# zik-pcb-sbc-ez80stm100p.net
KiCad netlist of a schematic drawn in EAGLE
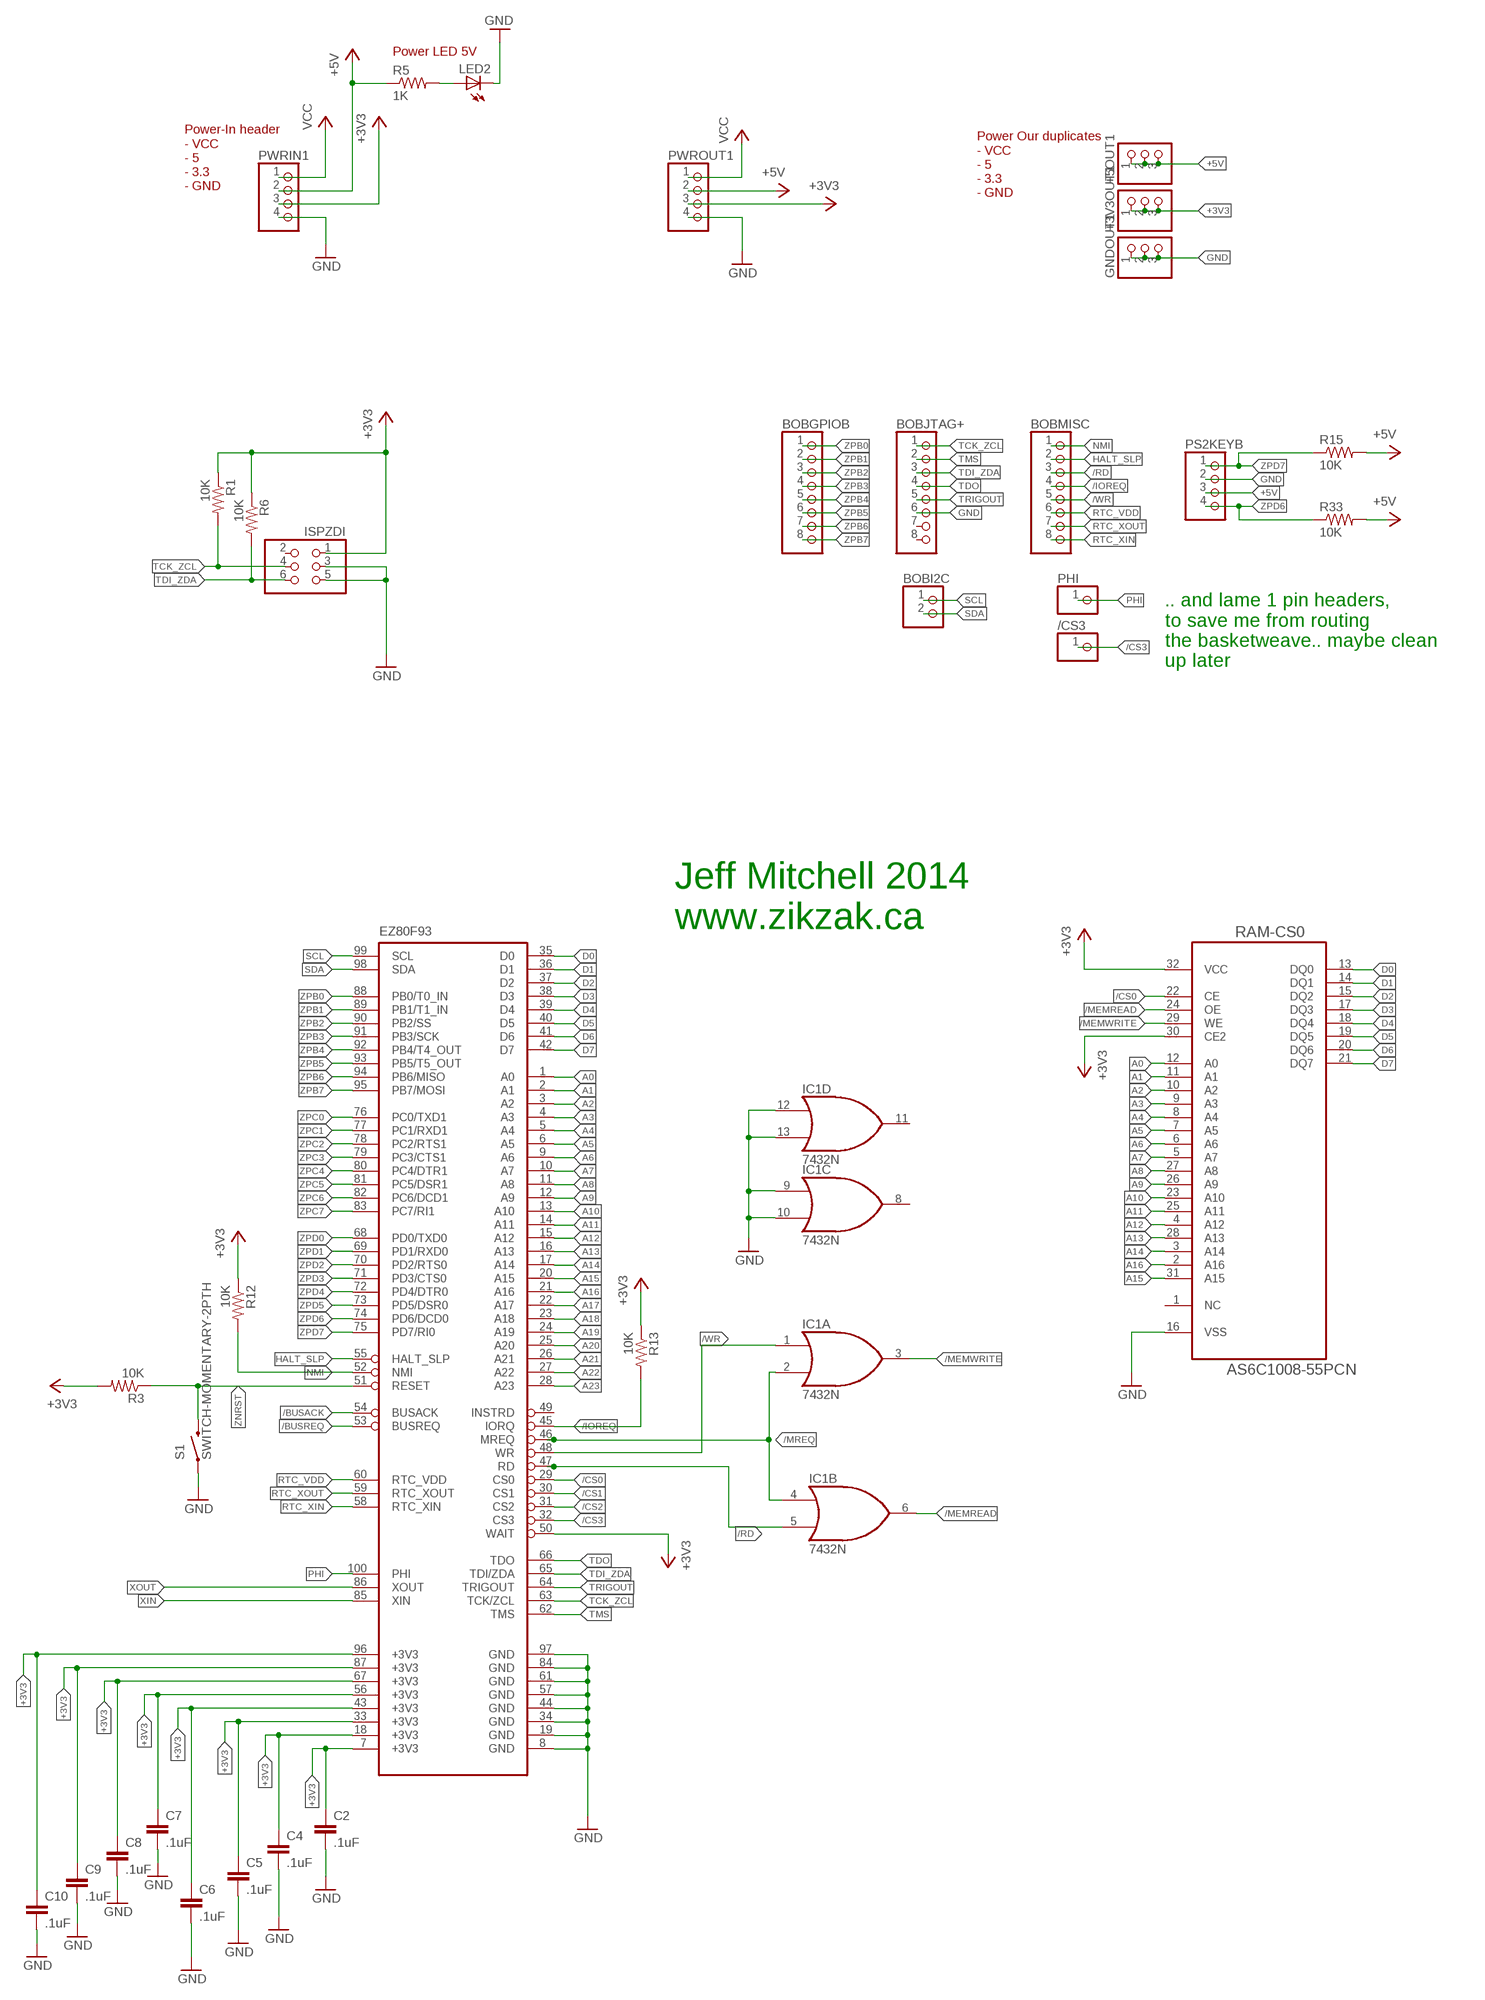
[diagram p0: schematic, sheet 1, part 1 of 3]
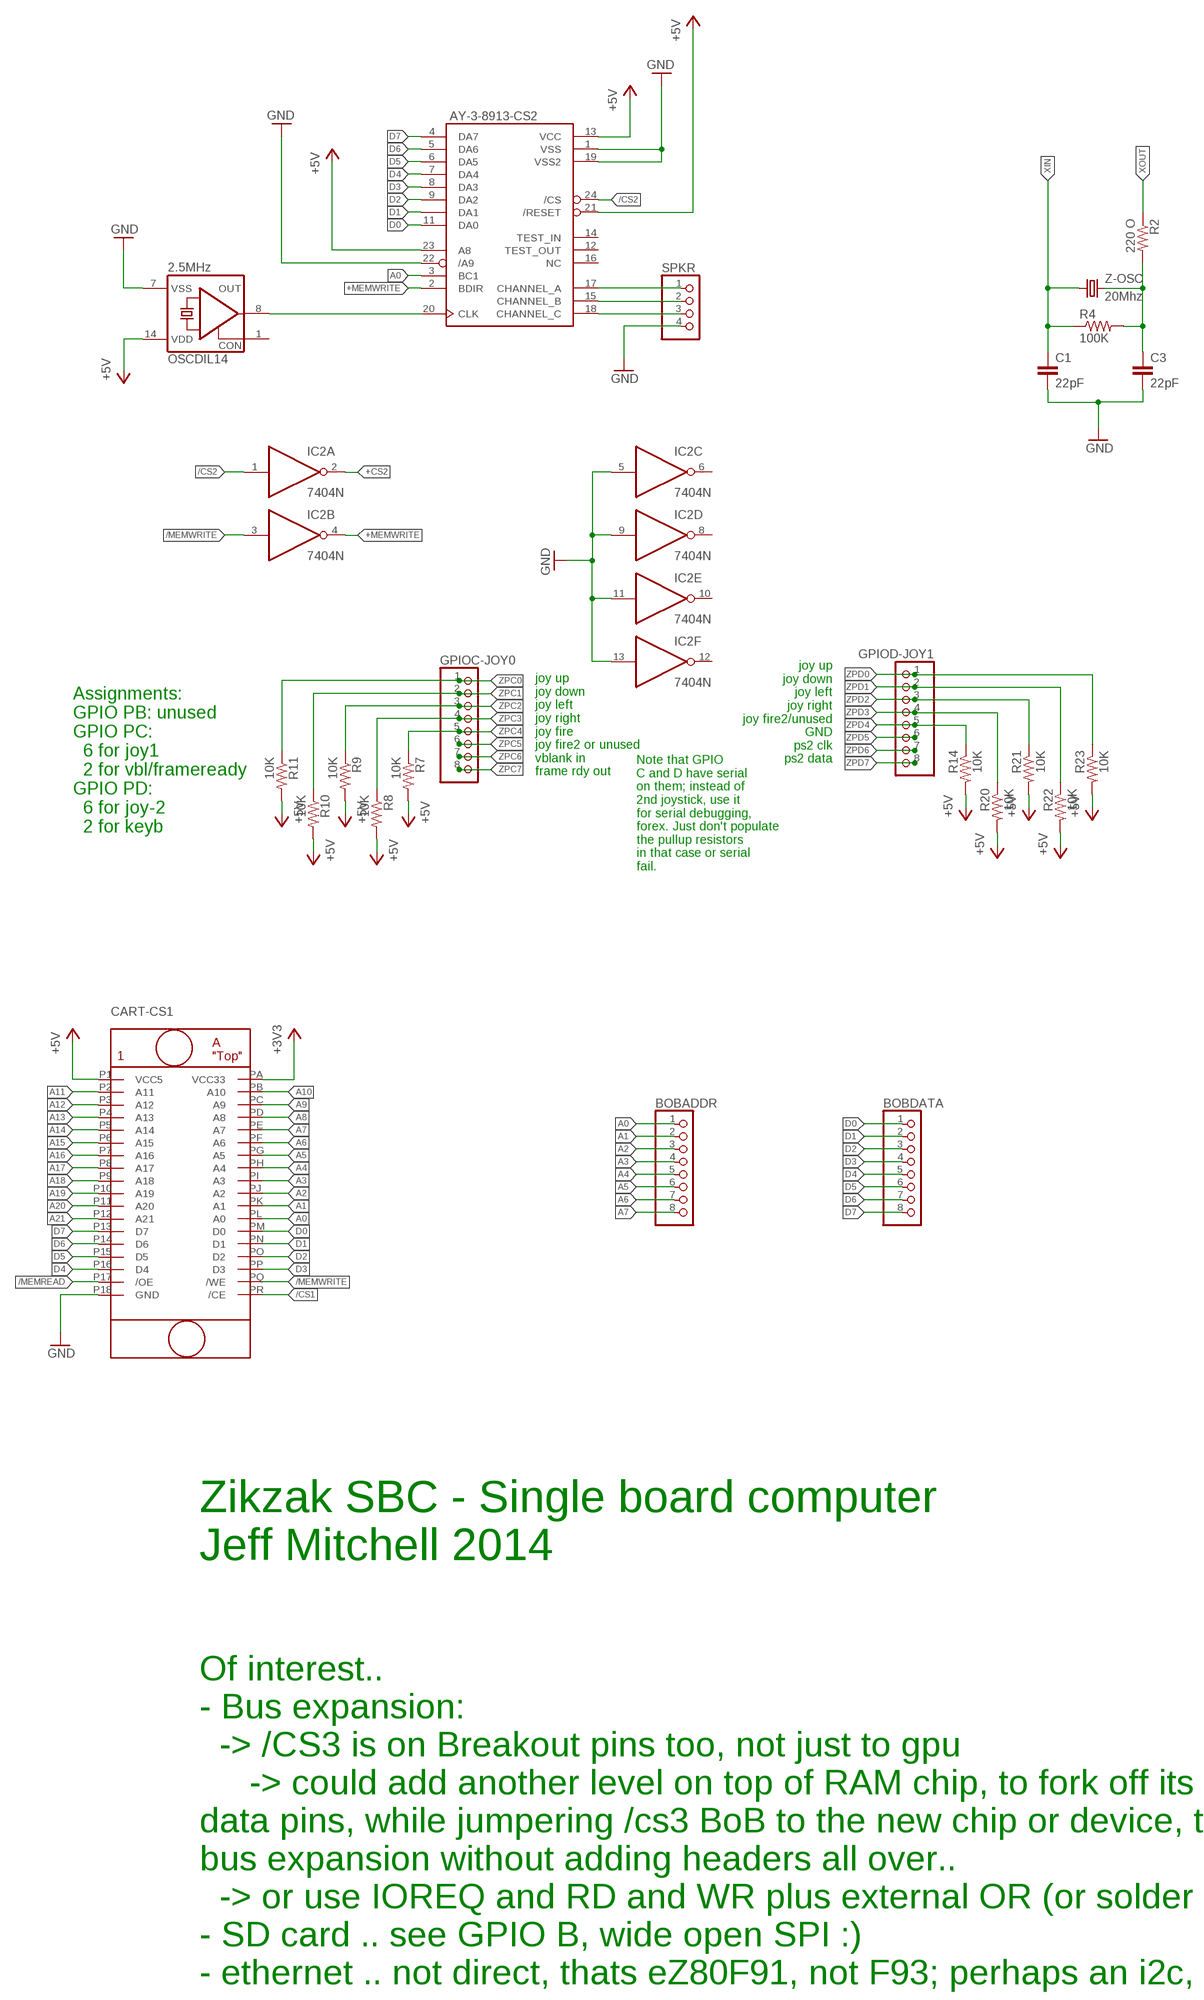
[diagram p1: schematic, sheet 1, part 2 of 3]
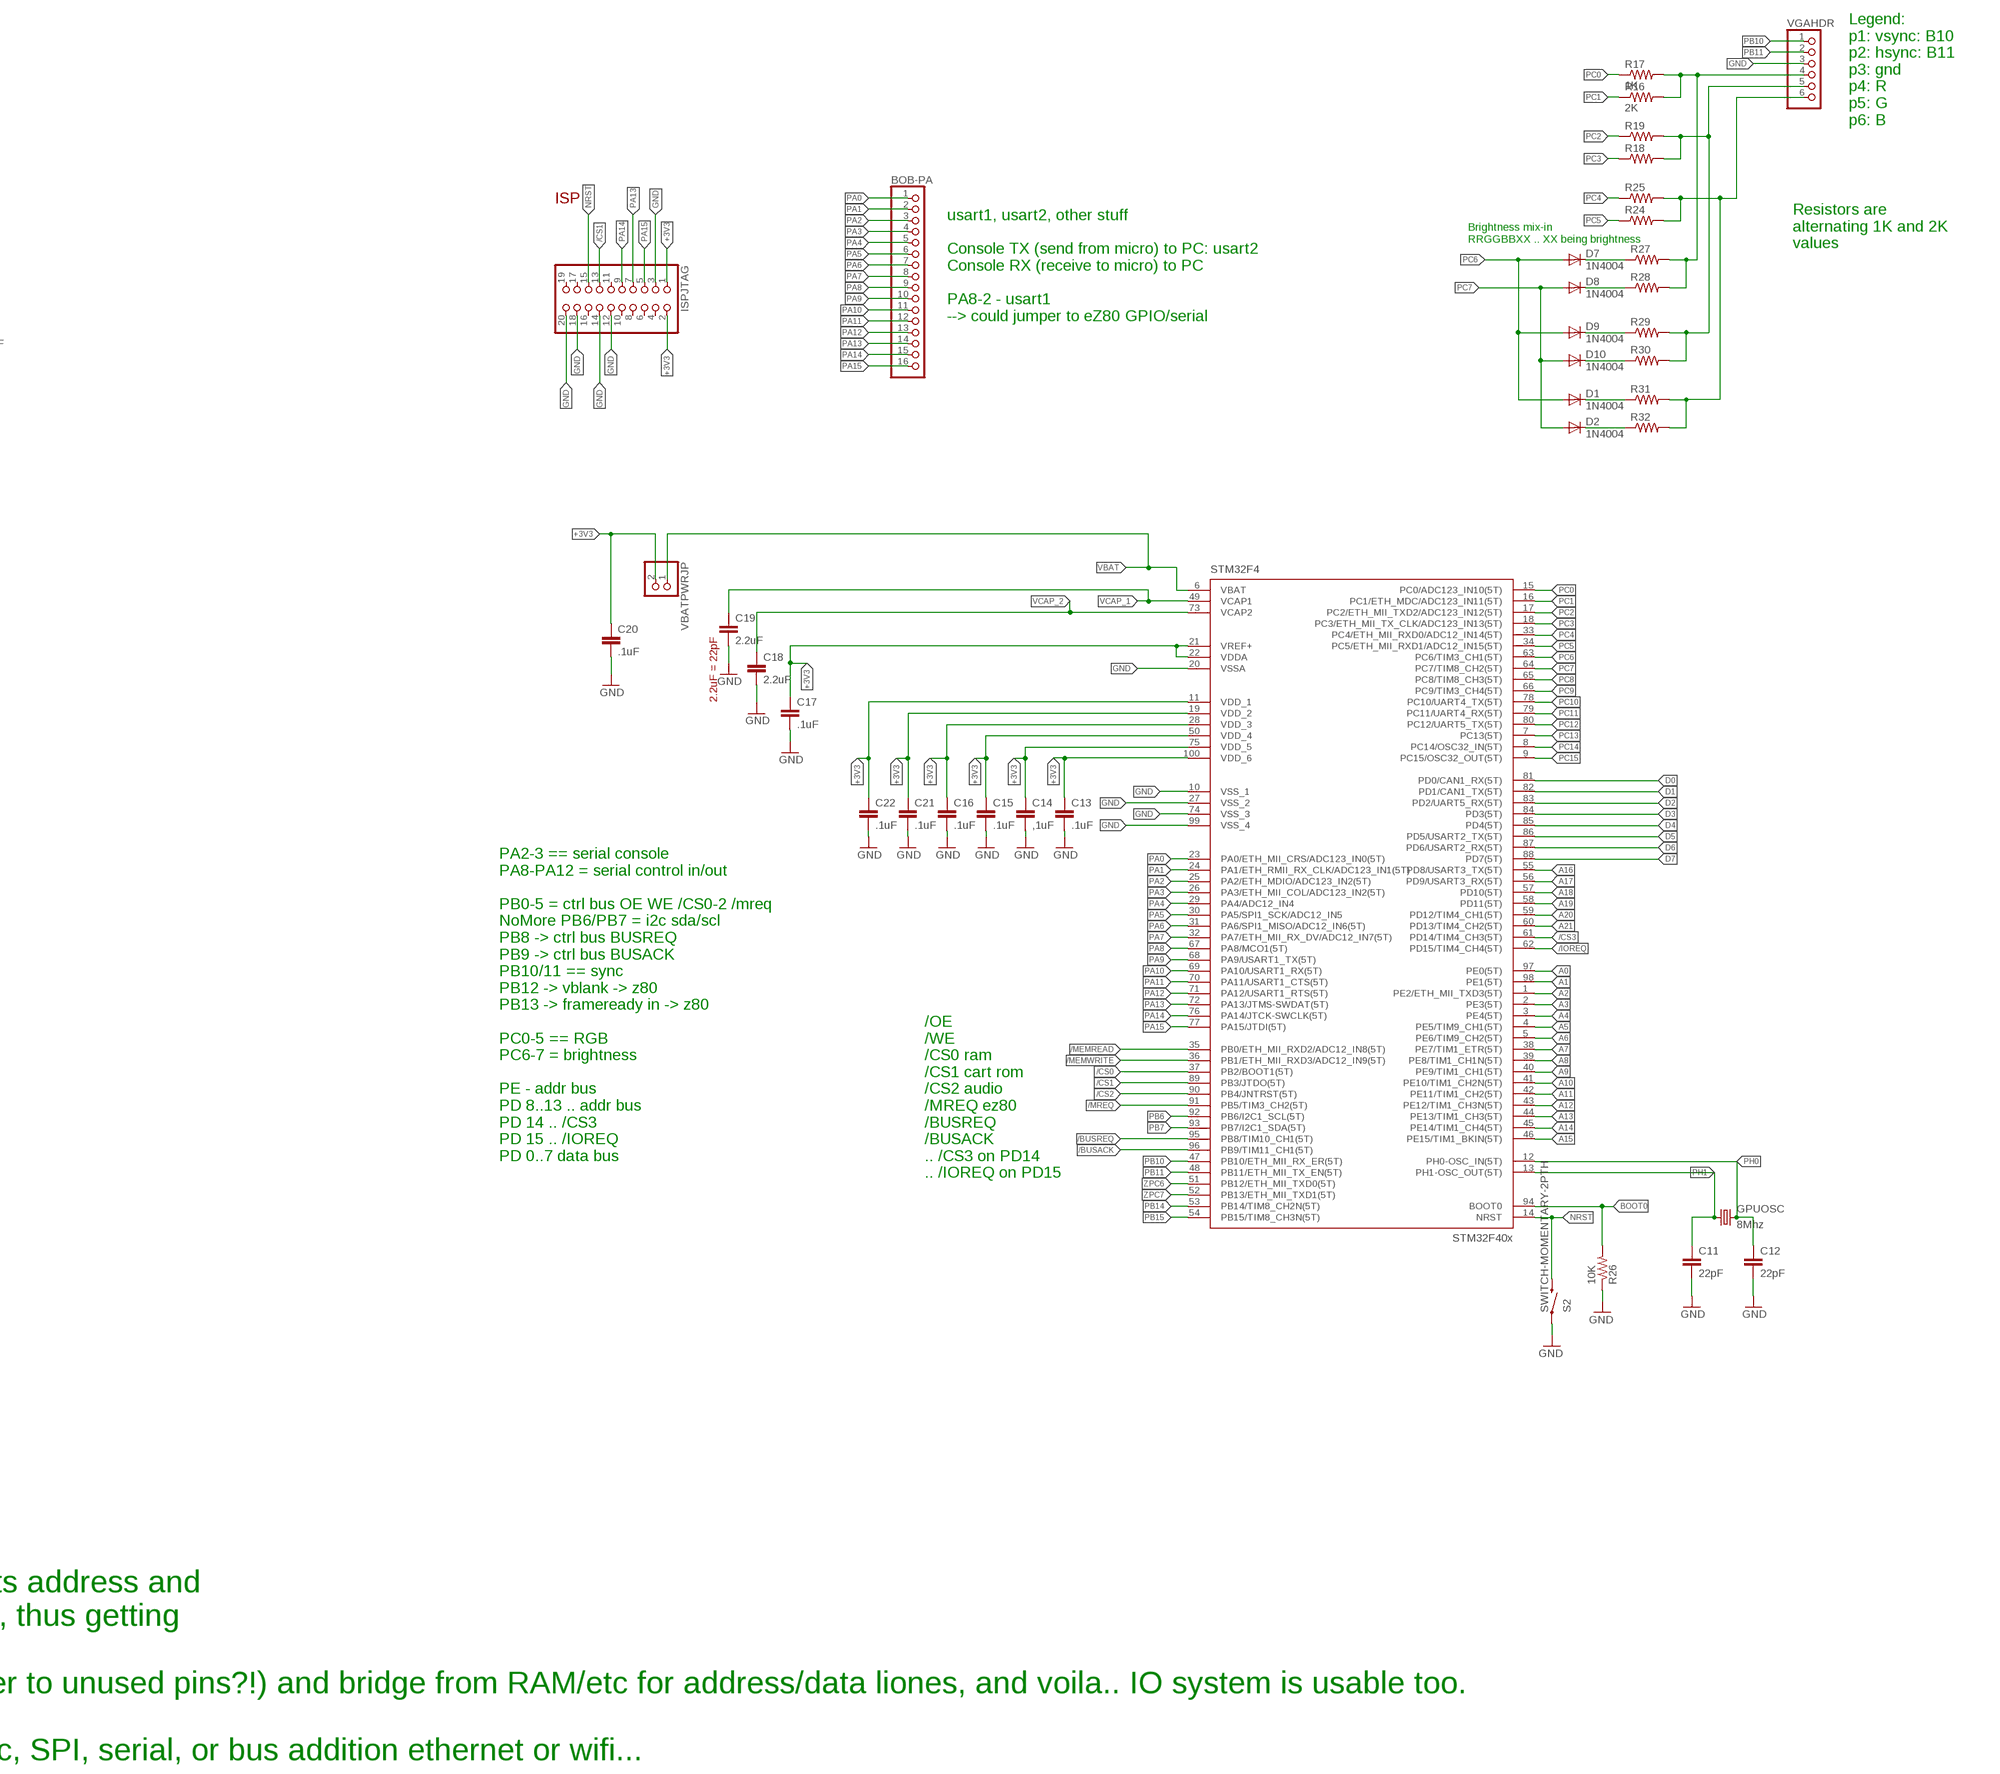
[diagram p2: schematic, sheet 1, part 3 of 3]

(export (version "E")
  (design (tool "Eeschema 10.0.6"))
  (components
    (comp (ref "+3V3OUT1")
      (value "PINHD-1X3")
      (footprint "eagle-import:1X03")
      (libsource (lib "eagle-import") (part "PINHD-1X3"))
    )
    (comp (ref "+5OUT1")
      (value "PINHD-1X3")
      (footprint "eagle-import:1X03")
      (libsource (lib "eagle-import") (part "PINHD-1X3"))
    )
    (comp (ref "/CS3")
      (value "PINHD-1X1")
      (footprint "eagle-import:1X01")
      (libsource (lib "eagle-import") (part "PINHD-1X1"))
    )
    (comp (ref "AY-3-8913-CS2")
      (value "AY-3-8912_24PIN-6")
      (footprint "eagle-import:DIL24-6")
      (libsource (lib "eagle-import") (part "AY-3-8912_24PIN-6"))
    )
    (comp (ref "BOB-PA")
      (value "PINHD-1X16")
      (footprint "eagle-import:1X16")
      (libsource (lib "eagle-import") (part "PINHD-1X16"))
    )
    (comp (ref "BOBADDR")
      (value "PINHD-1X8")
      (footprint "eagle-import:1X08")
      (libsource (lib "eagle-import") (part "PINHD-1X8"))
    )
    (comp (ref "BOBDATA")
      (value "PINHD-1X8")
      (footprint "eagle-import:1X08")
      (libsource (lib "eagle-import") (part "PINHD-1X8"))
    )
    (comp (ref "BOBGPIOB")
      (value "PINHD-1X8")
      (footprint "eagle-import:1X08")
      (libsource (lib "eagle-import") (part "PINHD-1X8"))
    )
    (comp (ref "BOBI2C")
      (value "PINHD-1X2")
      (footprint "eagle-import:1X02")
      (libsource (lib "eagle-import") (part "PINHD-1X2"))
    )
    (comp (ref "BOBJTAG+")
      (value "PINHD-1X8")
      (footprint "eagle-import:1X08")
      (libsource (lib "eagle-import") (part "PINHD-1X8"))
    )
    (comp (ref "BOBMISC")
      (value "PINHD-1X8")
      (footprint "eagle-import:1X08")
      (libsource (lib "eagle-import") (part "PINHD-1X8"))
    )
    (comp (ref "C1")
      (value "22pF")
      (footprint "eagle-import:C025-025X050")
      (libsource (lib "eagle-import") (part "C-EU025-025X050"))
    )
    (comp (ref "C2")
      (value ".1uF")
      (footprint "eagle-import:C025-025X050")
      (libsource (lib "eagle-import") (part "C-EU025-025X050"))
    )
    (comp (ref "C3")
      (value "22pF")
      (footprint "eagle-import:C025-025X050")
      (libsource (lib "eagle-import") (part "C-EU025-025X050"))
    )
    (comp (ref "C4")
      (value ".1uF")
      (footprint "eagle-import:C025-025X050")
      (libsource (lib "eagle-import") (part "C-EU025-025X050"))
    )
    (comp (ref "C5")
      (value ".1uF")
      (footprint "eagle-import:C025-025X050")
      (libsource (lib "eagle-import") (part "C-EU025-025X050"))
    )
    (comp (ref "C6")
      (value ".1uF")
      (footprint "eagle-import:C025-025X050")
      (libsource (lib "eagle-import") (part "C-EU025-025X050"))
    )
    (comp (ref "C7")
      (value ".1uF")
      (footprint "eagle-import:C025-025X050")
      (libsource (lib "eagle-import") (part "C-EU025-025X050"))
    )
    (comp (ref "C8")
      (value ".1uF")
      (footprint "eagle-import:C025-025X050")
      (libsource (lib "eagle-import") (part "C-EU025-025X050"))
    )
    (comp (ref "C9")
      (value ".1uF")
      (footprint "eagle-import:C025-025X050")
      (libsource (lib "eagle-import") (part "C-EU025-025X050"))
    )
    (comp (ref "C10")
      (value ".1uF")
      (footprint "eagle-import:C025-025X050")
      (libsource (lib "eagle-import") (part "C-EU025-025X050"))
    )
    (comp (ref "C11")
      (value "22pF")
      (footprint "eagle-import:C025-025X050")
      (libsource (lib "eagle-import") (part "C-EU025-025X050"))
    )
    (comp (ref "C12")
      (value "22pF")
      (footprint "eagle-import:C025-025X050")
      (libsource (lib "eagle-import") (part "C-EU025-025X050"))
    )
    (comp (ref "C13")
      (value ".1uF")
      (footprint "eagle-import:C025-025X050")
      (libsource (lib "eagle-import") (part "C-EU025-025X050"))
    )
    (comp (ref "C14")
      (value ",1uF")
      (footprint "eagle-import:C025-025X050")
      (libsource (lib "eagle-import") (part "C-EU025-025X050"))
    )
    (comp (ref "C15")
      (value ".1uF")
      (footprint "eagle-import:C025-025X050")
      (libsource (lib "eagle-import") (part "C-EU025-025X050"))
    )
    (comp (ref "C16")
      (value ".1uF")
      (footprint "eagle-import:C025-025X050")
      (libsource (lib "eagle-import") (part "C-EU025-025X050"))
    )
    (comp (ref "C17")
      (value ".1uF")
      (footprint "eagle-import:C025-025X050")
      (libsource (lib "eagle-import") (part "C-EU025-025X050"))
    )
    (comp (ref "C18")
      (value "2.2uF")
      (footprint "eagle-import:C025-025X050")
      (libsource (lib "eagle-import") (part "C-EU025-025X050"))
    )
    (comp (ref "C19")
      (value "2.2uF")
      (footprint "eagle-import:C025-025X050")
      (libsource (lib "eagle-import") (part "C-EU025-025X050"))
    )
    (comp (ref "C20")
      (value ".1uF")
      (footprint "eagle-import:C025-025X050")
      (libsource (lib "eagle-import") (part "C-EU025-025X050"))
    )
    (comp (ref "C21")
      (value ".1uF")
      (footprint "eagle-import:C025-025X050")
      (libsource (lib "eagle-import") (part "C-EU025-025X050"))
    )
    (comp (ref "C22")
      (value ".1uF")
      (footprint "eagle-import:C025-025X050")
      (libsource (lib "eagle-import") (part "C-EU025-025X050"))
    )
    (comp (ref "CART-CS1")
      (value "ZIKCART36")
      (footprint "eagle-import:ZIKCARTSLOT")
      (libsource (lib "eagle-import") (part "ZIKCART36"))
    )
    (comp (ref "D1")
      (value "1N4004")
      (footprint "eagle-import:DO41-10")
      (libsource (lib "eagle-import") (part "1N4004"))
    )
    (comp (ref "D2")
      (value "1N4004")
      (footprint "eagle-import:DO41-10")
      (libsource (lib "eagle-import") (part "1N4004"))
    )
    (comp (ref "D7")
      (value "1N4004")
      (footprint "eagle-import:DO41-10")
      (libsource (lib "eagle-import") (part "1N4004"))
    )
    (comp (ref "D8")
      (value "1N4004")
      (footprint "eagle-import:DO41-10")
      (libsource (lib "eagle-import") (part "1N4004"))
    )
    (comp (ref "D9")
      (value "1N4004")
      (footprint "eagle-import:DO41-10")
      (libsource (lib "eagle-import") (part "1N4004"))
    )
    (comp (ref "D10")
      (value "1N4004")
      (footprint "eagle-import:DO41-10")
      (libsource (lib "eagle-import") (part "1N4004"))
    )
    (comp (ref "EZ80F93")
      (value "EZ80F92AZ")
      (footprint "eagle-import:SQFP-S-14X14-100")
      (libsource (lib "eagle-import") (part "EZ80F92AZ"))
    )
    (comp (ref "GNDOUT1")
      (value "PINHD-1X3")
      (footprint "eagle-import:1X03")
      (libsource (lib "eagle-import") (part "PINHD-1X3"))
    )
    (comp (ref "GPIOC-JOY0")
      (value "PINHD-1X8")
      (footprint "eagle-import:1X08")
      (libsource (lib "eagle-import") (part "PINHD-1X8"))
    )
    (comp (ref "GPIOD-JOY1")
      (value "PINHD-1X8")
      (footprint "eagle-import:1X08")
      (libsource (lib "eagle-import") (part "PINHD-1X8"))
    )
    (comp (ref "GPUOSC")
      (value "8Mhz")
      (footprint "eagle-import:HC49US")
      (libsource (lib "eagle-import") (part "CRYSTALHC49US"))
    )
    (comp (ref "IC1")
      (value "7432N")
      (footprint "eagle-import:DIL14")
      (libsource (lib "eagle-import") (part "7432N"))
    )
    (comp (ref "IC2")
      (value "7404N")
      (footprint "eagle-import:DIL14")
      (libsource (lib "eagle-import") (part "7404N"))
    )
    (comp (ref "ISPJTAG")
      (value "PINHD-2X10")
      (footprint "eagle-import:2X10")
      (libsource (lib "eagle-import") (part "PINHD-2X10"))
    )
    (comp (ref "ISPZDI")
      (value "PINHD-2X3")
      (footprint "eagle-import:2X03")
      (libsource (lib "eagle-import") (part "PINHD-2X3"))
    )
    (comp (ref "LED2")
      (value "LED5MM")
      (footprint "eagle-import:LED5MM")
      (libsource (lib "eagle-import") (part "LED5MM"))
    )
    (comp (ref "OSCDIL14")
      (value "2.5MHz")
      (footprint "eagle-import:SG51")
      (libsource (lib "eagle-import") (part "CRYSTAL_RES-SG51"))
    )
    (comp (ref "PHI")
      (value "PINHD-1X1")
      (footprint "eagle-import:1X01")
      (libsource (lib "eagle-import") (part "PINHD-1X1"))
    )
    (comp (ref "PS2KEYB")
      (value "PINHD-1X4")
      (footprint "eagle-import:1X04")
      (libsource (lib "eagle-import") (part "PINHD-1X4"))
    )
    (comp (ref "PWRIN1")
      (value "PINHD-1X4")
      (footprint "eagle-import:1X04")
      (libsource (lib "eagle-import") (part "PINHD-1X4"))
    )
    (comp (ref "PWROUT1")
      (value "PINHD-1X4")
      (footprint "eagle-import:1X04")
      (libsource (lib "eagle-import") (part "PINHD-1X4"))
    )
    (comp (ref "R1")
      (value "10K")
      (footprint "eagle-import:0204_7")
      (libsource (lib "eagle-import") (part "R-US_0204/7"))
    )
    (comp (ref "R2")
      (value "220 O")
      (footprint "eagle-import:0204_7")
      (libsource (lib "eagle-import") (part "R-US_0204/7"))
    )
    (comp (ref "R3")
      (value "10K")
      (footprint "eagle-import:0204_7")
      (libsource (lib "eagle-import") (part "R-US_0204/7"))
    )
    (comp (ref "R4")
      (value "100K")
      (footprint "eagle-import:0204_7")
      (libsource (lib "eagle-import") (part "R-US_0204/7"))
    )
    (comp (ref "R5")
      (value "1K")
      (footprint "eagle-import:0207_10")
      (libsource (lib "eagle-import") (part "R-US_0207/10"))
    )
    (comp (ref "R6")
      (value "10K")
      (footprint "eagle-import:0204_7")
      (libsource (lib "eagle-import") (part "R-US_0204/7"))
    )
    (comp (ref "R7")
      (value "10K")
      (footprint "eagle-import:0204_7")
      (libsource (lib "eagle-import") (part "R-US_0204/7"))
    )
    (comp (ref "R8")
      (value "10K")
      (footprint "eagle-import:0204_7")
      (libsource (lib "eagle-import") (part "R-US_0204/7"))
    )
    (comp (ref "R9")
      (value "10K")
      (footprint "eagle-import:0204_7")
      (libsource (lib "eagle-import") (part "R-US_0204/7"))
    )
    (comp (ref "R10")
      (value "10K")
      (footprint "eagle-import:0204_7")
      (libsource (lib "eagle-import") (part "R-US_0204/7"))
    )
    (comp (ref "R11")
      (value "10K")
      (footprint "eagle-import:0204_7")
      (libsource (lib "eagle-import") (part "R-US_0204/7"))
    )
    (comp (ref "R12")
      (value "10K")
      (footprint "eagle-import:0204_7")
      (libsource (lib "eagle-import") (part "R-US_0204/7"))
    )
    (comp (ref "R13")
      (value "10K")
      (footprint "eagle-import:0204_7")
      (libsource (lib "eagle-import") (part "R-US_0204/7"))
    )
    (comp (ref "R14")
      (value "10K")
      (footprint "eagle-import:0204_7")
      (libsource (lib "eagle-import") (part "R-US_0204/7"))
    )
    (comp (ref "R15")
      (value "10K")
      (footprint "eagle-import:0204_7")
      (libsource (lib "eagle-import") (part "R-US_0204/7"))
    )
    (comp (ref "R16")
      (value "2K")
      (footprint "eagle-import:0207_10")
      (libsource (lib "eagle-import") (part "R-US_0207/10"))
    )
    (comp (ref "R17")
      (value "1K")
      (footprint "eagle-import:0207_10")
      (libsource (lib "eagle-import") (part "R-US_0207/10"))
    )
    (comp (ref "R18")
      (value "R-US_0207/10")
      (footprint "eagle-import:0207_10")
      (libsource (lib "eagle-import") (part "R-US_0207/10"))
    )
    (comp (ref "R19")
      (value "R-US_0207/10")
      (footprint "eagle-import:0207_10")
      (libsource (lib "eagle-import") (part "R-US_0207/10"))
    )
    (comp (ref "R20")
      (value "10K")
      (footprint "eagle-import:0204_7")
      (libsource (lib "eagle-import") (part "R-US_0204/7"))
    )
    (comp (ref "R21")
      (value "10K")
      (footprint "eagle-import:0204_7")
      (libsource (lib "eagle-import") (part "R-US_0204/7"))
    )
    (comp (ref "R22")
      (value "10K")
      (footprint "eagle-import:0204_7")
      (libsource (lib "eagle-import") (part "R-US_0204/7"))
    )
    (comp (ref "R23")
      (value "10K")
      (footprint "eagle-import:0204_7")
      (libsource (lib "eagle-import") (part "R-US_0204/7"))
    )
    (comp (ref "R24")
      (value "R-US_0207/10")
      (footprint "eagle-import:0207_10")
      (libsource (lib "eagle-import") (part "R-US_0207/10"))
    )
    (comp (ref "R25")
      (value "R-US_0207/10")
      (footprint "eagle-import:0207_10")
      (libsource (lib "eagle-import") (part "R-US_0207/10"))
    )
    (comp (ref "R26")
      (value "10K")
      (footprint "eagle-import:0207_10")
      (libsource (lib "eagle-import") (part "R-US_0207/10"))
    )
    (comp (ref "R27")
      (value "R-US_0207/10")
      (footprint "eagle-import:0207_10")
      (libsource (lib "eagle-import") (part "R-US_0207/10"))
    )
    (comp (ref "R28")
      (value "R-US_0207/10")
      (footprint "eagle-import:0207_10")
      (libsource (lib "eagle-import") (part "R-US_0207/10"))
    )
    (comp (ref "R29")
      (value "R-US_0207/10")
      (footprint "eagle-import:0207_10")
      (libsource (lib "eagle-import") (part "R-US_0207/10"))
    )
    (comp (ref "R30")
      (value "R-US_0207/10")
      (footprint "eagle-import:0207_10")
      (libsource (lib "eagle-import") (part "R-US_0207/10"))
    )
    (comp (ref "R31")
      (value "R-US_0207/10")
      (footprint "eagle-import:0207_10")
      (libsource (lib "eagle-import") (part "R-US_0207/10"))
    )
    (comp (ref "R32")
      (value "R-US_0207/10")
      (footprint "eagle-import:0207_10")
      (libsource (lib "eagle-import") (part "R-US_0207/10"))
    )
    (comp (ref "R33")
      (value "10K")
      (footprint "eagle-import:0204_7")
      (libsource (lib "eagle-import") (part "R-US_0204/7"))
    )
    (comp (ref "RAM-CS0")
      (value "AS6C1008-55PCN")
      (footprint "eagle-import:DIP254P1524X393-32")
      (libsource (lib "eagle-import") (part "AS6C1008-55PCN"))
    )
    (comp (ref "S1")
      (value "SWITCH-MOMENTARY-2PTH")
      (footprint "eagle-import:TACTILE-PTH")
      (libsource (lib "eagle-import") (part "SWITCH-MOMENTARY-2PTH"))
    )
    (comp (ref "S2")
      (value "SWITCH-MOMENTARY-2PTH")
      (footprint "eagle-import:TACTILE-PTH")
      (libsource (lib "eagle-import") (part "SWITCH-MOMENTARY-2PTH"))
    )
    (comp (ref "SPKR")
      (value "PINHD-1X4")
      (footprint "eagle-import:1X04")
      (libsource (lib "eagle-import") (part "PINHD-1X4"))
    )
    (comp (ref "STM32F4")
      (value "STM32F407V")
      (footprint "eagle-import:TQFP100")
      (libsource (lib "eagle-import") (part "STM32F407V"))
    )
    (comp (ref "VBATPWRJP")
      (value "PINHD-1X2")
      (footprint "eagle-import:1X02")
      (libsource (lib "eagle-import") (part "PINHD-1X2"))
    )
    (comp (ref "VGAHDR")
      (value "PINHD-1X6")
      (footprint "eagle-import:1X06")
      (libsource (lib "eagle-import") (part "PINHD-1X6"))
    )
    (comp (ref "Z-OSC")
      (value "20Mhz")
      (footprint "eagle-import:HC49US")
      (libsource (lib "eagle-import") (part "CRYSTALHC49US"))
    )
  )
  (nets
    (net (code "1") (name "+3V3") (class "Default")
      (node (ref "+3V3OUT1") (pin "1") (pinfunction "1_1") (pintype "passive"))
      (node (ref "+3V3OUT1") (pin "2") (pinfunction "2_2") (pintype "passive"))
      (node (ref "+3V3OUT1") (pin "3") (pinfunction "3_3") (pintype "passive"))
      (node (ref "C10") (pin "1") (pinfunction "1_1") (pintype "passive"))
      (node (ref "C13") (pin "1") (pinfunction "1_1") (pintype "passive"))
      (node (ref "C14") (pin "1") (pinfunction "1_1") (pintype "passive"))
      (node (ref "C15") (pin "1") (pinfunction "1_1") (pintype "passive"))
      (node (ref "C16") (pin "1") (pinfunction "1_1") (pintype "passive"))
      (node (ref "C17") (pin "1") (pinfunction "1_1") (pintype "passive"))
      (node (ref "C2") (pin "1") (pinfunction "1_1") (pintype "passive"))
      (node (ref "C20") (pin "1") (pinfunction "1_1") (pintype "passive"))
      (node (ref "C21") (pin "1") (pinfunction "1_1") (pintype "passive"))
      (node (ref "C22") (pin "1") (pinfunction "1_1") (pintype "passive"))
      (node (ref "C4") (pin "1") (pinfunction "1_1") (pintype "passive"))
      (node (ref "C5") (pin "1") (pinfunction "1_1") (pintype "passive"))
      (node (ref "C6") (pin "1") (pinfunction "1_1") (pintype "passive"))
      (node (ref "C7") (pin "1") (pinfunction "1_1") (pintype "passive"))
      (node (ref "C8") (pin "1") (pinfunction "1_1") (pintype "passive"))
      (node (ref "C9") (pin "1") (pinfunction "1_1") (pintype "passive"))
      (node (ref "CART-CS1") (pin "PA") (pinfunction "VCC33_PA") (pintype "bidirectional"))
      (node (ref "EZ80F93") (pin "18") (pinfunction "+3V3_18") (pintype "power_in"))
      (node (ref "EZ80F93") (pin "33") (pinfunction "+3V3_33") (pintype "power_in"))
      (node (ref "EZ80F93") (pin "43") (pinfunction "+3V3_43") (pintype "power_in"))
      (node (ref "EZ80F93") (pin "50") (pinfunction "WAIT_50") (pintype "input"))
      (node (ref "EZ80F93") (pin "56") (pinfunction "+3V3_56") (pintype "power_in"))
      (node (ref "EZ80F93") (pin "67") (pinfunction "+3V3_67") (pintype "power_in"))
      (node (ref "EZ80F93") (pin "7") (pinfunction "+3V3_7") (pintype "power_in"))
      (node (ref "EZ80F93") (pin "87") (pinfunction "+3V3_87") (pintype "power_in"))
      (node (ref "EZ80F93") (pin "96") (pinfunction "+3V3_96") (pintype "power_in"))
      (node (ref "ISPJTAG") (pin "1") (pinfunction "1_1") (pintype "passive"))
      (node (ref "ISPJTAG") (pin "2") (pinfunction "2_2") (pintype "passive"))
      (node (ref "ISPZDI") (pin "1") (pinfunction "1_1") (pintype "passive"))
      (node (ref "PWRIN1") (pin "3") (pinfunction "3_3") (pintype "passive"))
      (node (ref "PWROUT1") (pin "3") (pinfunction "3_3") (pintype "passive"))
      (node (ref "R1") (pin "1") (pinfunction "1_1") (pintype "passive"))
      (node (ref "R12") (pin "1") (pinfunction "1_1") (pintype "passive"))
      (node (ref "R13") (pin "1") (pinfunction "1_1") (pintype "passive"))
      (node (ref "R3") (pin "2") (pinfunction "2_2") (pintype "passive"))
      (node (ref "R6") (pin "1") (pinfunction "1_1") (pintype "passive"))
      (node (ref "RAM-CS0") (pin "30") (pinfunction "CE2_30") (pintype "input"))
      (node (ref "RAM-CS0") (pin "32") (pinfunction "VCC_32") (pintype "power_in"))
      (node (ref "STM32F4") (pin "100") (pinfunction "VDD_6_100") (pintype "bidirectional"))
      (node (ref "STM32F4") (pin "11") (pinfunction "VDD_1_11") (pintype "bidirectional"))
      (node (ref "STM32F4") (pin "19") (pinfunction "VDD_2_19") (pintype "bidirectional"))
      (node (ref "STM32F4") (pin "21") (pinfunction "VREF+_21") (pintype "bidirectional"))
      (node (ref "STM32F4") (pin "22") (pinfunction "VDDA_22") (pintype "bidirectional"))
      (node (ref "STM32F4") (pin "28") (pinfunction "VDD_3_28") (pintype "bidirectional"))
      (node (ref "STM32F4") (pin "50") (pinfunction "VDD_4_50") (pintype "bidirectional"))
      (node (ref "STM32F4") (pin "75") (pinfunction "VDD_5_75") (pintype "bidirectional"))
      (node (ref "VBATPWRJP") (pin "2") (pinfunction "2_2") (pintype "passive"))
    )
    (net (code "2") (name "+5V") (class "Default")
      (node (ref "+5OUT1") (pin "1") (pinfunction "1_1") (pintype "passive"))
      (node (ref "+5OUT1") (pin "2") (pinfunction "2_2") (pintype "passive"))
      (node (ref "+5OUT1") (pin "3") (pinfunction "3_3") (pintype "passive"))
      (node (ref "AY-3-8913-CS2") (pin "13") (pinfunction "VCC_13") (pintype "power_in"))
      (node (ref "AY-3-8913-CS2") (pin "21") (pinfunction "/RESET_21") (pintype "input"))
      (node (ref "AY-3-8913-CS2") (pin "23") (pinfunction "A8_23") (pintype "input"))
      (node (ref "CART-CS1") (pin "P1") (pinfunction "VCC5_P1") (pintype "bidirectional"))
      (node (ref "OSCDIL14") (pin "14") (pinfunction "VDD_14") (pintype "power_in"))
      (node (ref "PS2KEYB") (pin "3") (pinfunction "3_3") (pintype "passive"))
      (node (ref "PWRIN1") (pin "2") (pinfunction "2_2") (pintype "passive"))
      (node (ref "PWROUT1") (pin "2") (pinfunction "2_2") (pintype "passive"))
      (node (ref "R10") (pin "2") (pinfunction "2_2") (pintype "passive"))
      (node (ref "R11") (pin "2") (pinfunction "2_2") (pintype "passive"))
      (node (ref "R14") (pin "2") (pinfunction "2_2") (pintype "passive"))
      (node (ref "R15") (pin "2") (pinfunction "2_2") (pintype "passive"))
      (node (ref "R20") (pin "2") (pinfunction "2_2") (pintype "passive"))
      (node (ref "R21") (pin "2") (pinfunction "2_2") (pintype "passive"))
      (node (ref "R22") (pin "2") (pinfunction "2_2") (pintype "passive"))
      (node (ref "R23") (pin "2") (pinfunction "2_2") (pintype "passive"))
      (node (ref "R33") (pin "2") (pinfunction "2_2") (pintype "passive"))
      (node (ref "R5") (pin "1") (pinfunction "1_1") (pintype "passive"))
      (node (ref "R7") (pin "2") (pinfunction "2_2") (pintype "passive"))
      (node (ref "R8") (pin "2") (pinfunction "2_2") (pintype "passive"))
      (node (ref "R9") (pin "2") (pinfunction "2_2") (pintype "passive"))
    )
    (net (code "3") (name "+CS2") (class "Default")
      (node (ref "IC2") (pin "2") (pinfunction "O_2") (pintype "output"))
    )
    (net (code "4") (name "+MEMWRITE") (class "Default")
      (node (ref "AY-3-8913-CS2") (pin "2") (pinfunction "BDIR_2") (pintype "input"))
      (node (ref "IC2") (pin "4") (pinfunction "O_4") (pintype "output"))
    )
    (net (code "5") (name "A0") (class "Default")
      (node (ref "AY-3-8913-CS2") (pin "3") (pinfunction "BC1_3") (pintype "input"))
      (node (ref "BOBADDR") (pin "1") (pinfunction "1_1") (pintype "passive"))
      (node (ref "CART-CS1") (pin "PL") (pinfunction "A0_PL") (pintype "bidirectional"))
      (node (ref "EZ80F93") (pin "1") (pinfunction "A0_1") (pintype "bidirectional"))
      (node (ref "RAM-CS0") (pin "12") (pinfunction "A0_12") (pintype "input"))
      (node (ref "STM32F4") (pin "97") (pinfunction "PE0(5T)_97") (pintype "bidirectional"))
    )
    (net (code "6") (name "A1") (class "Default")
      (node (ref "BOBADDR") (pin "2") (pinfunction "2_2") (pintype "passive"))
      (node (ref "CART-CS1") (pin "PK") (pinfunction "A1_PK") (pintype "bidirectional"))
      (node (ref "EZ80F93") (pin "2") (pinfunction "A1_2") (pintype "bidirectional"))
      (node (ref "RAM-CS0") (pin "11") (pinfunction "A1_11") (pintype "input"))
      (node (ref "STM32F4") (pin "98") (pinfunction "PE1(5T)_98") (pintype "bidirectional"))
    )
    (net (code "7") (name "A2") (class "Default")
      (node (ref "BOBADDR") (pin "3") (pinfunction "3_3") (pintype "passive"))
      (node (ref "CART-CS1") (pin "PJ") (pinfunction "A2_PJ") (pintype "bidirectional"))
      (node (ref "EZ80F93") (pin "3") (pinfunction "A2_3") (pintype "bidirectional"))
      (node (ref "RAM-CS0") (pin "10") (pinfunction "A2_10") (pintype "input"))
      (node (ref "STM32F4") (pin "1") (pinfunction "PE2/ETH_MII_TXD3(5T)_1") (pintype "bidirectional"))
    )
    (net (code "8") (name "A3") (class "Default")
      (node (ref "BOBADDR") (pin "4") (pinfunction "4_4") (pintype "passive"))
      (node (ref "CART-CS1") (pin "PI") (pinfunction "A3_PI") (pintype "bidirectional"))
      (node (ref "EZ80F93") (pin "4") (pinfunction "A3_4") (pintype "bidirectional"))
      (node (ref "RAM-CS0") (pin "9") (pinfunction "A3_9") (pintype "input"))
      (node (ref "STM32F4") (pin "2") (pinfunction "PE3(5T)_2") (pintype "bidirectional"))
    )
    (net (code "9") (name "A4") (class "Default")
      (node (ref "BOBADDR") (pin "5") (pinfunction "5_5") (pintype "passive"))
      (node (ref "CART-CS1") (pin "PH") (pinfunction "A4_PH") (pintype "bidirectional"))
      (node (ref "EZ80F93") (pin "5") (pinfunction "A4_5") (pintype "bidirectional"))
      (node (ref "RAM-CS0") (pin "8") (pinfunction "A4_8") (pintype "input"))
      (node (ref "STM32F4") (pin "3") (pinfunction "PE4(5T)_3") (pintype "bidirectional"))
    )
    (net (code "10") (name "A5") (class "Default")
      (node (ref "BOBADDR") (pin "6") (pinfunction "6_6") (pintype "passive"))
      (node (ref "CART-CS1") (pin "PG") (pinfunction "A5_PG") (pintype "bidirectional"))
      (node (ref "EZ80F93") (pin "6") (pinfunction "A5_6") (pintype "bidirectional"))
      (node (ref "RAM-CS0") (pin "7") (pinfunction "A5_7") (pintype "input"))
      (node (ref "STM32F4") (pin "4") (pinfunction "PE5/TIM9_CH1(5T)_4") (pintype "bidirectional"))
    )
    (net (code "11") (name "A6") (class "Default")
      (node (ref "BOBADDR") (pin "7") (pinfunction "7_7") (pintype "passive"))
      (node (ref "CART-CS1") (pin "PF") (pinfunction "A6_PF") (pintype "bidirectional"))
      (node (ref "EZ80F93") (pin "9") (pinfunction "A6_9") (pintype "bidirectional"))
      (node (ref "RAM-CS0") (pin "6") (pinfunction "A6_6") (pintype "input"))
      (node (ref "STM32F4") (pin "5") (pinfunction "PE6/TIM9_CH2(5T)_5") (pintype "bidirectional"))
    )
    (net (code "12") (name "A7") (class "Default")
      (node (ref "BOBADDR") (pin "8") (pinfunction "8_8") (pintype "passive"))
      (node (ref "CART-CS1") (pin "PE") (pinfunction "A7_PE") (pintype "bidirectional"))
      (node (ref "EZ80F93") (pin "10") (pinfunction "A7_10") (pintype "bidirectional"))
      (node (ref "RAM-CS0") (pin "5") (pinfunction "A7_5") (pintype "input"))
      (node (ref "STM32F4") (pin "38") (pinfunction "PE7/TIM1_ETR(5T)_38") (pintype "bidirectional"))
    )
    (net (code "13") (name "A8") (class "Default")
      (node (ref "CART-CS1") (pin "PD") (pinfunction "A8_PD") (pintype "bidirectional"))
      (node (ref "EZ80F93") (pin "11") (pinfunction "A8_11") (pintype "bidirectional"))
      (node (ref "RAM-CS0") (pin "27") (pinfunction "A8_27") (pintype "input"))
      (node (ref "STM32F4") (pin "39") (pinfunction "PE8/TIM1_CH1N(5T)_39") (pintype "bidirectional"))
    )
    (net (code "14") (name "A9") (class "Default")
      (node (ref "CART-CS1") (pin "PC") (pinfunction "A9_PC") (pintype "bidirectional"))
      (node (ref "EZ80F93") (pin "12") (pinfunction "A9_12") (pintype "bidirectional"))
      (node (ref "RAM-CS0") (pin "26") (pinfunction "A9_26") (pintype "input"))
      (node (ref "STM32F4") (pin "40") (pinfunction "PE9/TIM1_CH1(5T)_40") (pintype "bidirectional"))
    )
    (net (code "15") (name "A10") (class "Default")
      (node (ref "CART-CS1") (pin "PB") (pinfunction "A10_PB") (pintype "bidirectional"))
      (node (ref "EZ80F93") (pin "13") (pinfunction "A10_13") (pintype "bidirectional"))
      (node (ref "RAM-CS0") (pin "23") (pinfunction "A10_23") (pintype "input"))
      (node (ref "STM32F4") (pin "41") (pinfunction "PE10/TIM1_CH2N(5T)_41") (pintype "bidirectional"))
    )
    (net (code "16") (name "A11") (class "Default")
      (node (ref "CART-CS1") (pin "P2") (pinfunction "A11_P2") (pintype "bidirectional"))
      (node (ref "EZ80F93") (pin "14") (pinfunction "A11_14") (pintype "bidirectional"))
      (node (ref "RAM-CS0") (pin "25") (pinfunction "A11_25") (pintype "input"))
      (node (ref "STM32F4") (pin "42") (pinfunction "PE11/TIM1_CH2(5T)_42") (pintype "bidirectional"))
    )
    (net (code "17") (name "A12") (class "Default")
      (node (ref "CART-CS1") (pin "P3") (pinfunction "A12_P3") (pintype "bidirectional"))
      (node (ref "EZ80F93") (pin "15") (pinfunction "A12_15") (pintype "bidirectional"))
      (node (ref "RAM-CS0") (pin "4") (pinfunction "A12_4") (pintype "input"))
      (node (ref "STM32F4") (pin "43") (pinfunction "PE12/TIM1_CH3N(5T)_43") (pintype "bidirectional"))
    )
    (net (code "18") (name "A13") (class "Default")
      (node (ref "CART-CS1") (pin "P4") (pinfunction "A13_P4") (pintype "bidirectional"))
      (node (ref "EZ80F93") (pin "16") (pinfunction "A13_16") (pintype "bidirectional"))
      (node (ref "RAM-CS0") (pin "28") (pinfunction "A13_28") (pintype "input"))
      (node (ref "STM32F4") (pin "44") (pinfunction "PE13/TIM1_CH3(5T)_44") (pintype "bidirectional"))
    )
    (net (code "19") (name "A14") (class "Default")
      (node (ref "CART-CS1") (pin "P5") (pinfunction "A14_P5") (pintype "bidirectional"))
      (node (ref "EZ80F93") (pin "17") (pinfunction "A14_17") (pintype "bidirectional"))
      (node (ref "RAM-CS0") (pin "3") (pinfunction "A14_3") (pintype "input"))
      (node (ref "STM32F4") (pin "45") (pinfunction "PE14/TIM1_CH4(5T)_45") (pintype "bidirectional"))
    )
    (net (code "20") (name "A15") (class "Default")
      (node (ref "CART-CS1") (pin "P6") (pinfunction "A15_P6") (pintype "bidirectional"))
      (node (ref "EZ80F93") (pin "20") (pinfunction "A15_20") (pintype "bidirectional"))
      (node (ref "RAM-CS0") (pin "31") (pinfunction "A15_31") (pintype "input"))
      (node (ref "STM32F4") (pin "46") (pinfunction "PE15/TIM1_BKIN(5T)_46") (pintype "bidirectional"))
    )
    (net (code "21") (name "A16") (class "Default")
      (node (ref "CART-CS1") (pin "P7") (pinfunction "A16_P7") (pintype "bidirectional"))
      (node (ref "EZ80F93") (pin "21") (pinfunction "A16_21") (pintype "bidirectional"))
      (node (ref "RAM-CS0") (pin "2") (pinfunction "A16_2") (pintype "input"))
      (node (ref "STM32F4") (pin "55") (pinfunction "PD8/USART3_TX(5T)_55") (pintype "bidirectional"))
    )
    (net (code "22") (name "A17") (class "Default")
      (node (ref "CART-CS1") (pin "P8") (pinfunction "A17_P8") (pintype "bidirectional"))
      (node (ref "EZ80F93") (pin "22") (pinfunction "A17_22") (pintype "bidirectional"))
      (node (ref "STM32F4") (pin "56") (pinfunction "PD9/USART3_RX(5T)_56") (pintype "bidirectional"))
    )
    (net (code "23") (name "A18") (class "Default")
      (node (ref "CART-CS1") (pin "P9") (pinfunction "A18_P9") (pintype "bidirectional"))
      (node (ref "EZ80F93") (pin "23") (pinfunction "A18_23") (pintype "bidirectional"))
      (node (ref "STM32F4") (pin "57") (pinfunction "PD10(5T)_57") (pintype "bidirectional"))
    )
    (net (code "24") (name "A19") (class "Default")
      (node (ref "CART-CS1") (pin "P10") (pinfunction "A19_P10") (pintype "bidirectional"))
      (node (ref "EZ80F93") (pin "24") (pinfunction "A19_24") (pintype "bidirectional"))
      (node (ref "STM32F4") (pin "58") (pinfunction "PD11(5T)_58") (pintype "bidirectional"))
    )
    (net (code "25") (name "A20") (class "Default")
      (node (ref "CART-CS1") (pin "P11") (pinfunction "A20_P11") (pintype "bidirectional"))
      (node (ref "EZ80F93") (pin "25") (pinfunction "A20_25") (pintype "bidirectional"))
      (node (ref "STM32F4") (pin "59") (pinfunction "PD12/TIM4_CH1(5T)_59") (pintype "bidirectional"))
    )
    (net (code "26") (name "A21") (class "Default")
      (node (ref "CART-CS1") (pin "P12") (pinfunction "A21_P12") (pintype "bidirectional"))
      (node (ref "EZ80F93") (pin "26") (pinfunction "A21_26") (pintype "bidirectional"))
      (node (ref "STM32F4") (pin "60") (pinfunction "PD13/TIM4_CH2(5T)_60") (pintype "bidirectional"))
    )
    (net (code "27") (name "A22") (class "Default")
      (node (ref "EZ80F93") (pin "27") (pinfunction "A22_27") (pintype "bidirectional"))
    )
    (net (code "28") (name "A23") (class "Default")
      (node (ref "EZ80F93") (pin "28") (pinfunction "A23_28") (pintype "bidirectional"))
    )
    (net (code "29") (name "BOOT0") (class "Default")
      (node (ref "R26") (pin "2") (pinfunction "2_2") (pintype "passive"))
      (node (ref "STM32F4") (pin "94") (pinfunction "BOOT0_94") (pintype "bidirectional"))
    )
    (net (code "30") (name "D0") (class "Default")
      (node (ref "AY-3-8913-CS2") (pin "11") (pinfunction "DA0_11") (pintype "bidirectional"))
      (node (ref "BOBDATA") (pin "1") (pinfunction "1_1") (pintype "passive"))
      (node (ref "CART-CS1") (pin "PM") (pinfunction "D0_PM") (pintype "bidirectional"))
      (node (ref "EZ80F93") (pin "35") (pinfunction "D0_35") (pintype "bidirectional"))
      (node (ref "RAM-CS0") (pin "13") (pinfunction "DQ0_13") (pintype "bidirectional"))
      (node (ref "STM32F4") (pin "81") (pinfunction "PD0/CAN1_RX(5T)_81") (pintype "bidirectional"))
    )
    (net (code "31") (name "D1") (class "Default")
      (node (ref "AY-3-8913-CS2") (pin "10") (pinfunction "DA1_10") (pintype "bidirectional"))
      (node (ref "BOBDATA") (pin "2") (pinfunction "2_2") (pintype "passive"))
      (node (ref "CART-CS1") (pin "PN") (pinfunction "D1_PN") (pintype "bidirectional"))
      (node (ref "EZ80F93") (pin "36") (pinfunction "D1_36") (pintype "bidirectional"))
      (node (ref "RAM-CS0") (pin "14") (pinfunction "DQ1_14") (pintype "bidirectional"))
      (node (ref "STM32F4") (pin "82") (pinfunction "PD1/CAN1_TX(5T)_82") (pintype "bidirectional"))
    )
    (net (code "32") (name "D2") (class "Default")
      (node (ref "AY-3-8913-CS2") (pin "9") (pinfunction "DA2_9") (pintype "bidirectional"))
      (node (ref "BOBDATA") (pin "3") (pinfunction "3_3") (pintype "passive"))
      (node (ref "CART-CS1") (pin "PO") (pinfunction "D2_PO") (pintype "bidirectional"))
      (node (ref "EZ80F93") (pin "37") (pinfunction "D2_37") (pintype "bidirectional"))
      (node (ref "RAM-CS0") (pin "15") (pinfunction "DQ2_15") (pintype "bidirectional"))
      (node (ref "STM32F4") (pin "83") (pinfunction "PD2/UART5_RX(5T)_83") (pintype "bidirectional"))
    )
    (net (code "33") (name "D3") (class "Default")
      (node (ref "AY-3-8913-CS2") (pin "8") (pinfunction "DA3_8") (pintype "bidirectional"))
      (node (ref "BOBDATA") (pin "4") (pinfunction "4_4") (pintype "passive"))
      (node (ref "CART-CS1") (pin "PP") (pinfunction "D3_PP") (pintype "bidirectional"))
      (node (ref "EZ80F93") (pin "38") (pinfunction "D3_38") (pintype "bidirectional"))
      (node (ref "RAM-CS0") (pin "17") (pinfunction "DQ3_17") (pintype "bidirectional"))
      (node (ref "STM32F4") (pin "84") (pinfunction "PD3(5T)_84") (pintype "bidirectional"))
    )
    (net (code "34") (name "D4") (class "Default")
      (node (ref "AY-3-8913-CS2") (pin "7") (pinfunction "DA4_7") (pintype "bidirectional"))
      (node (ref "BOBDATA") (pin "5") (pinfunction "5_5") (pintype "passive"))
      (node (ref "CART-CS1") (pin "P16") (pinfunction "D4_P16") (pintype "bidirectional"))
      (node (ref "EZ80F93") (pin "39") (pinfunction "D4_39") (pintype "bidirectional"))
      (node (ref "RAM-CS0") (pin "18") (pinfunction "DQ4_18") (pintype "bidirectional"))
      (node (ref "STM32F4") (pin "85") (pinfunction "PD4(5T)_85") (pintype "bidirectional"))
    )
    (net (code "35") (name "D5") (class "Default")
      (node (ref "AY-3-8913-CS2") (pin "6") (pinfunction "DA5_6") (pintype "bidirectional"))
      (node (ref "BOBDATA") (pin "6") (pinfunction "6_6") (pintype "passive"))
      (node (ref "CART-CS1") (pin "P15") (pinfunction "D5_P15") (pintype "bidirectional"))
      (node (ref "EZ80F93") (pin "40") (pinfunction "D5_40") (pintype "bidirectional"))
      (node (ref "RAM-CS0") (pin "19") (pinfunction "DQ5_19") (pintype "bidirectional"))
      (node (ref "STM32F4") (pin "86") (pinfunction "PD5/USART2_TX(5T)_86") (pintype "bidirectional"))
    )
    (net (code "36") (name "D6") (class "Default")
      (node (ref "AY-3-8913-CS2") (pin "5") (pinfunction "DA6_5") (pintype "bidirectional"))
      (node (ref "BOBDATA") (pin "7") (pinfunction "7_7") (pintype "passive"))
      (node (ref "CART-CS1") (pin "P14") (pinfunction "D6_P14") (pintype "bidirectional"))
      (node (ref "EZ80F93") (pin "41") (pinfunction "D6_41") (pintype "bidirectional"))
      (node (ref "RAM-CS0") (pin "20") (pinfunction "DQ6_20") (pintype "bidirectional"))
      (node (ref "STM32F4") (pin "87") (pinfunction "PD6/USART2_RX(5T)_87") (pintype "bidirectional"))
    )
    (net (code "37") (name "D7") (class "Default")
      (node (ref "AY-3-8913-CS2") (pin "4") (pinfunction "DA7_4") (pintype "bidirectional"))
      (node (ref "BOBDATA") (pin "8") (pinfunction "8_8") (pintype "passive"))
      (node (ref "CART-CS1") (pin "P13") (pinfunction "D7_P13") (pintype "bidirectional"))
      (node (ref "EZ80F93") (pin "42") (pinfunction "D7_42") (pintype "bidirectional"))
      (node (ref "RAM-CS0") (pin "21") (pinfunction "DQ7_21") (pintype "bidirectional"))
      (node (ref "STM32F4") (pin "88") (pinfunction "PD7(5T)_88") (pintype "bidirectional"))
    )
    (net (code "38") (name "GND") (class "Default")
      (node (ref "AY-3-8913-CS2") (pin "1") (pinfunction "VSS_1") (pintype "power_in"))
      (node (ref "AY-3-8913-CS2") (pin "19") (pinfunction "VSS2_19") (pintype "power_in"))
      (node (ref "AY-3-8913-CS2") (pin "22") (pinfunction "/A9_22") (pintype "input"))
      (node (ref "BOBJTAG+") (pin "6") (pinfunction "6_6") (pintype "passive"))
      (node (ref "C1") (pin "2") (pinfunction "2_2") (pintype "passive"))
      (node (ref "C10") (pin "2") (pinfunction "2_2") (pintype "passive"))
      (node (ref "C11") (pin "2") (pinfunction "2_2") (pintype "passive"))
      (node (ref "C12") (pin "2") (pinfunction "2_2") (pintype "passive"))
      (node (ref "C13") (pin "2") (pinfunction "2_2") (pintype "passive"))
      (node (ref "C14") (pin "2") (pinfunction "2_2") (pintype "passive"))
      (node (ref "C15") (pin "2") (pinfunction "2_2") (pintype "passive"))
      (node (ref "C16") (pin "2") (pinfunction "2_2") (pintype "passive"))
      (node (ref "C17") (pin "2") (pinfunction "2_2") (pintype "passive"))
      (node (ref "C18") (pin "2") (pinfunction "2_2") (pintype "passive"))
      (node (ref "C19") (pin "2") (pinfunction "2_2") (pintype "passive"))
      (node (ref "C2") (pin "2") (pinfunction "2_2") (pintype "passive"))
      (node (ref "C20") (pin "2") (pinfunction "2_2") (pintype "passive"))
      (node (ref "C21") (pin "2") (pinfunction "2_2") (pintype "passive"))
      (node (ref "C22") (pin "2") (pinfunction "2_2") (pintype "passive"))
      (node (ref "C3") (pin "2") (pinfunction "2_2") (pintype "passive"))
      (node (ref "C4") (pin "2") (pinfunction "2_2") (pintype "passive"))
      (node (ref "C5") (pin "2") (pinfunction "2_2") (pintype "passive"))
      (node (ref "C6") (pin "2") (pinfunction "2_2") (pintype "passive"))
      (node (ref "C7") (pin "2") (pinfunction "2_2") (pintype "passive"))
      (node (ref "C8") (pin "2") (pinfunction "2_2") (pintype "passive"))
      (node (ref "C9") (pin "2") (pinfunction "2_2") (pintype "passive"))
      (node (ref "CART-CS1") (pin "P18") (pinfunction "GND_P18") (pintype "bidirectional"))
      (node (ref "EZ80F93") (pin "19") (pinfunction "GND_19") (pintype "power_in"))
      (node (ref "EZ80F93") (pin "34") (pinfunction "GND_34") (pintype "power_in"))
      (node (ref "EZ80F93") (pin "44") (pinfunction "GND_44") (pintype "power_in"))
      (node (ref "EZ80F93") (pin "57") (pinfunction "GND_57") (pintype "power_in"))
      (node (ref "EZ80F93") (pin "61") (pinfunction "GND_61") (pintype "power_in"))
      (node (ref "EZ80F93") (pin "8") (pinfunction "GND_8") (pintype "power_in"))
      (node (ref "EZ80F93") (pin "84") (pinfunction "GND_84") (pintype "power_in"))
      (node (ref "EZ80F93") (pin "97") (pinfunction "GND_97") (pintype "power_in"))
      (node (ref "GNDOUT1") (pin "1") (pinfunction "1_1") (pintype "passive"))
      (node (ref "GNDOUT1") (pin "2") (pinfunction "2_2") (pintype "passive"))
      (node (ref "GNDOUT1") (pin "3") (pinfunction "3_3") (pintype "passive"))
      (node (ref "IC1") (pin "10") (pinfunction "I1_10") (pintype "input"))
      (node (ref "IC1") (pin "12") (pinfunction "I0_12") (pintype "input"))
      (node (ref "IC1") (pin "13") (pinfunction "I1_13") (pintype "input"))
      (node (ref "IC1") (pin "9") (pinfunction "I0_9") (pintype "input"))
      (node (ref "IC2") (pin "11") (pinfunction "I_11") (pintype "input"))
      (node (ref "IC2") (pin "13") (pinfunction "I_13") (pintype "input"))
      (node (ref "IC2") (pin "5") (pinfunction "I_5") (pintype "input"))
      (node (ref "IC2") (pin "9") (pinfunction "I_9") (pintype "input"))
      (node (ref "ISPJTAG") (pin "12") (pinfunction "12_12") (pintype "passive"))
      (node (ref "ISPJTAG") (pin "14") (pinfunction "14_14") (pintype "passive"))
      (node (ref "ISPJTAG") (pin "18") (pinfunction "18_18") (pintype "passive"))
      (node (ref "ISPJTAG") (pin "20") (pinfunction "20_20") (pintype "passive"))
      (node (ref "ISPJTAG") (pin "3") (pinfunction "3_3") (pintype "passive"))
      (node (ref "ISPZDI") (pin "3") (pinfunction "3_3") (pintype "passive"))
      (node (ref "ISPZDI") (pin "5") (pinfunction "5_5") (pintype "passive"))
      (node (ref "LED2") (pin "K") (pinfunction "C_K") (pintype "passive"))
      (node (ref "OSCDIL14") (pin "7") (pinfunction "VSS_7") (pintype "power_in"))
      (node (ref "PS2KEYB") (pin "2") (pinfunction "2_2") (pintype "passive"))
      (node (ref "PWRIN1") (pin "4") (pinfunction "4_4") (pintype "passive"))
      (node (ref "PWROUT1") (pin "4") (pinfunction "4_4") (pintype "passive"))
      (node (ref "R26") (pin "1") (pinfunction "1_1") (pintype "passive"))
      (node (ref "RAM-CS0") (pin "16") (pinfunction "VSS_16") (pintype "bidirectional"))
      (node (ref "S1") (pin "1") (pinfunction "1_1") (pintype "passive"))
      (node (ref "S2") (pin "1") (pinfunction "1_1") (pintype "passive"))
      (node (ref "SPKR") (pin "4") (pinfunction "4_4") (pintype "passive"))
      (node (ref "STM32F4") (pin "10") (pinfunction "VSS_1_10") (pintype "bidirectional"))
      (node (ref "STM32F4") (pin "20") (pinfunction "VSSA_20") (pintype "bidirectional"))
      (node (ref "STM32F4") (pin "27") (pinfunction "VSS_2_27") (pintype "bidirectional"))
      (node (ref "STM32F4") (pin "74") (pinfunction "VSS_3_74") (pintype "bidirectional"))
      (node (ref "STM32F4") (pin "99") (pinfunction "VSS_4_99") (pintype "bidirectional"))
      (node (ref "VGAHDR") (pin "3") (pinfunction "3_3") (pintype "passive"))
    )
    (net (code "39") (name "HALT_SLP") (class "Default")
      (node (ref "BOBMISC") (pin "2") (pinfunction "2_2") (pintype "passive"))
      (node (ref "EZ80F93") (pin "55") (pinfunction "HALT_SLP_55") (pintype "output"))
    )
    (net (code "40") (name "NMI") (class "Default")
      (node (ref "BOBMISC") (pin "1") (pinfunction "1_1") (pintype "passive"))
      (node (ref "EZ80F93") (pin "52") (pinfunction "NMI_52") (pintype "input"))
      (node (ref "R12") (pin "2") (pinfunction "2_2") (pintype "passive"))
    )
    (net (code "41") (name "NRST") (class "Default")
      (node (ref "ISPJTAG") (pin "15") (pinfunction "15_15") (pintype "passive"))
      (node (ref "S2") (pin "3") (pinfunction "2_3") (pintype "passive"))
      (node (ref "STM32F4") (pin "14") (pinfunction "NRST_14") (pintype "bidirectional"))
    )
    (net (code "42") (name "Net-(AY-3-8913-CS2-CHANNEL_A)") (class "Default")
      (node (ref "AY-3-8913-CS2") (pin "17") (pinfunction "CHANNEL_A_17") (pintype "output"))
      (node (ref "SPKR") (pin "1") (pinfunction "1_1") (pintype "passive"))
    )
    (net (code "43") (name "Net-(AY-3-8913-CS2-CHANNEL_B)") (class "Default")
      (node (ref "AY-3-8913-CS2") (pin "15") (pinfunction "CHANNEL_B_15") (pintype "output"))
      (node (ref "SPKR") (pin "2") (pinfunction "2_2") (pintype "passive"))
    )
    (net (code "44") (name "Net-(AY-3-8913-CS2-CHANNEL_C)") (class "Default")
      (node (ref "AY-3-8913-CS2") (pin "18") (pinfunction "CHANNEL_C_18") (pintype "output"))
      (node (ref "SPKR") (pin "3") (pinfunction "3_3") (pintype "passive"))
    )
    (net (code "45") (name "Net-(AY-3-8913-CS2-CLK)") (class "Default")
      (node (ref "AY-3-8913-CS2") (pin "20") (pinfunction "CLK_20") (pintype "input"))
      (node (ref "OSCDIL14") (pin "8") (pinfunction "OUT_8") (pintype "output"))
    )
    (net (code "46") (name "Net-(C3-Pad1)") (class "Default")
      (node (ref "C3") (pin "1") (pinfunction "1_1") (pintype "passive"))
      (node (ref "R2") (pin "2") (pinfunction "2_2") (pintype "passive"))
      (node (ref "R4") (pin "2") (pinfunction "2_2") (pintype "passive"))
      (node (ref "Z-OSC") (pin "2") (pinfunction "2_2") (pintype "passive"))
    )
    (net (code "47") (name "Net-(D1-PadC)") (class "Default")
      (node (ref "D1") (pin "C") (pinfunction "C_C") (pintype "passive"))
      (node (ref "R31") (pin "1") (pinfunction "1_1") (pintype "passive"))
    )
    (net (code "48") (name "Net-(D2-PadC)") (class "Default")
      (node (ref "D2") (pin "C") (pinfunction "C_C") (pintype "passive"))
      (node (ref "R32") (pin "1") (pinfunction "1_1") (pintype "passive"))
    )
    (net (code "49") (name "Net-(D7-PadC)") (class "Default")
      (node (ref "D7") (pin "C") (pinfunction "C_C") (pintype "passive"))
      (node (ref "R27") (pin "1") (pinfunction "1_1") (pintype "passive"))
    )
    (net (code "50") (name "Net-(D8-PadC)") (class "Default")
      (node (ref "D8") (pin "C") (pinfunction "C_C") (pintype "passive"))
      (node (ref "R28") (pin "1") (pinfunction "1_1") (pintype "passive"))
    )
    (net (code "51") (name "Net-(D9-PadC)") (class "Default")
      (node (ref "D9") (pin "C") (pinfunction "C_C") (pintype "passive"))
      (node (ref "R29") (pin "1") (pinfunction "1_1") (pintype "passive"))
    )
    (net (code "52") (name "Net-(D10-PadC)") (class "Default")
      (node (ref "D10") (pin "C") (pinfunction "C_C") (pintype "passive"))
      (node (ref "R30") (pin "1") (pinfunction "1_1") (pintype "passive"))
    )
    (net (code "53") (name "Net-(LED2-PadA)") (class "Default")
      (node (ref "LED2") (pin "A") (pinfunction "A_A") (pintype "passive"))
      (node (ref "R5") (pin "2") (pinfunction "2_2") (pintype "passive"))
    )
    (net (code "54") (name "Net-(R16-Pad2)") (class "Default")
      (node (ref "R16") (pin "2") (pinfunction "2_2") (pintype "passive"))
      (node (ref "R17") (pin "2") (pinfunction "2_2") (pintype "passive"))
      (node (ref "R27") (pin "2") (pinfunction "2_2") (pintype "passive"))
      (node (ref "R28") (pin "2") (pinfunction "2_2") (pintype "passive"))
      (node (ref "VGAHDR") (pin "4") (pinfunction "4_4") (pintype "passive"))
    )
    (net (code "55") (name "Net-(R18-Pad2)") (class "Default")
      (node (ref "R18") (pin "2") (pinfunction "2_2") (pintype "passive"))
      (node (ref "R19") (pin "2") (pinfunction "2_2") (pintype "passive"))
      (node (ref "R29") (pin "2") (pinfunction "2_2") (pintype "passive"))
      (node (ref "R30") (pin "2") (pinfunction "2_2") (pintype "passive"))
      (node (ref "VGAHDR") (pin "5") (pinfunction "5_5") (pintype "passive"))
    )
    (net (code "56") (name "Net-(R24-Pad2)") (class "Default")
      (node (ref "R24") (pin "2") (pinfunction "2_2") (pintype "passive"))
      (node (ref "R25") (pin "2") (pinfunction "2_2") (pintype "passive"))
      (node (ref "R31") (pin "2") (pinfunction "2_2") (pintype "passive"))
      (node (ref "R32") (pin "2") (pinfunction "2_2") (pintype "passive"))
      (node (ref "VGAHDR") (pin "6") (pinfunction "6_6") (pintype "passive"))
    )
    (net (code "57") (name "PA0") (class "Default")
      (node (ref "BOB-PA") (pin "1") (pinfunction "1_1") (pintype "passive"))
      (node (ref "STM32F4") (pin "23") (pinfunction "PA0/ETH_MII_CRS/ADC123_IN0(5T)_23") (pintype "bidirectional"))
    )
    (net (code "58") (name "PA1") (class "Default")
      (node (ref "BOB-PA") (pin "2") (pinfunction "2_2") (pintype "passive"))
      (node (ref "STM32F4") (pin "24") (pinfunction "PA1/ETH_RMII_RX_CLK/ADC123_IN1(5T)_24") (pintype "bidirectional"))
    )
    (net (code "59") (name "PA2") (class "Default")
      (node (ref "BOB-PA") (pin "3") (pinfunction "3_3") (pintype "passive"))
      (node (ref "STM32F4") (pin "25") (pinfunction "PA2/ETH_MDIO/ADC123_IN2(5T)_25") (pintype "bidirectional"))
    )
    (net (code "60") (name "PA3") (class "Default")
      (node (ref "BOB-PA") (pin "4") (pinfunction "4_4") (pintype "passive"))
      (node (ref "STM32F4") (pin "26") (pinfunction "PA3/ETH_MII_COL/ADC123_IN2(5T)_26") (pintype "bidirectional"))
    )
    (net (code "61") (name "PA4") (class "Default")
      (node (ref "BOB-PA") (pin "5") (pinfunction "5_5") (pintype "passive"))
      (node (ref "STM32F4") (pin "29") (pinfunction "PA4/ADC12_IN4_29") (pintype "bidirectional"))
    )
    (net (code "62") (name "PA5") (class "Default")
      (node (ref "BOB-PA") (pin "6") (pinfunction "6_6") (pintype "passive"))
      (node (ref "STM32F4") (pin "30") (pinfunction "PA5/SPI1_SCK/ADC12_IN5_30") (pintype "bidirectional"))
    )
    (net (code "63") (name "PA6") (class "Default")
      (node (ref "BOB-PA") (pin "7") (pinfunction "7_7") (pintype "passive"))
      (node (ref "STM32F4") (pin "31") (pinfunction "PA6/SPI1_MISO/ADC12_IN6(5T)_31") (pintype "bidirectional"))
    )
    (net (code "64") (name "PA7") (class "Default")
      (node (ref "BOB-PA") (pin "8") (pinfunction "8_8") (pintype "passive"))
      (node (ref "STM32F4") (pin "32") (pinfunction "PA7/ETH_MII_RX_DV/ADC12_IN7(5T)_32") (pintype "bidirectional"))
    )
    (net (code "65") (name "PA8") (class "Default")
      (node (ref "BOB-PA") (pin "9") (pinfunction "9_9") (pintype "passive"))
      (node (ref "STM32F4") (pin "67") (pinfunction "PA8/MCO1(5T)_67") (pintype "bidirectional"))
    )
    (net (code "66") (name "PA9") (class "Default")
      (node (ref "BOB-PA") (pin "10") (pinfunction "10_10") (pintype "passive"))
      (node (ref "STM32F4") (pin "68") (pinfunction "PA9/USART1_TX(5T)_68") (pintype "bidirectional"))
    )
    (net (code "67") (name "PA10") (class "Default")
      (node (ref "BOB-PA") (pin "11") (pinfunction "11_11") (pintype "passive"))
      (node (ref "STM32F4") (pin "69") (pinfunction "PA10/USART1_RX(5T)_69") (pintype "bidirectional"))
    )
    (net (code "68") (name "PA11") (class "Default")
      (node (ref "BOB-PA") (pin "12") (pinfunction "12_12") (pintype "passive"))
      (node (ref "STM32F4") (pin "70") (pinfunction "PA11/USART1_CTS(5T)_70") (pintype "bidirectional"))
    )
    (net (code "69") (name "PA12") (class "Default")
      (node (ref "BOB-PA") (pin "13") (pinfunction "13_13") (pintype "passive"))
      (node (ref "STM32F4") (pin "71") (pinfunction "PA12/USART1_RTS(5T)_71") (pintype "bidirectional"))
    )
    (net (code "70") (name "PA13") (class "Default")
      (node (ref "BOB-PA") (pin "14") (pinfunction "14_14") (pintype "passive"))
      (node (ref "ISPJTAG") (pin "7") (pinfunction "7_7") (pintype "passive"))
      (node (ref "STM32F4") (pin "72") (pinfunction "PA13/JTMS-SWDAT(5T)_72") (pintype "bidirectional"))
    )
    (net (code "71") (name "PA14") (class "Default")
      (node (ref "BOB-PA") (pin "15") (pinfunction "15_15") (pintype "passive"))
      (node (ref "ISPJTAG") (pin "9") (pinfunction "9_9") (pintype "passive"))
      (node (ref "STM32F4") (pin "76") (pinfunction "PA14/JTCK-SWCLK(5T)_76") (pintype "bidirectional"))
    )
    (net (code "72") (name "PA15") (class "Default")
      (node (ref "BOB-PA") (pin "16") (pinfunction "16_16") (pintype "passive"))
      (node (ref "ISPJTAG") (pin "5") (pinfunction "5_5") (pintype "passive"))
      (node (ref "STM32F4") (pin "77") (pinfunction "PA15/JTDI(5T)_77") (pintype "bidirectional"))
    )
    (net (code "73") (name "PB6") (class "Default")
      (node (ref "STM32F4") (pin "92") (pinfunction "PB6/I2C1_SCL(5T)_92") (pintype "bidirectional"))
    )
    (net (code "74") (name "PB7") (class "Default")
      (node (ref "STM32F4") (pin "93") (pinfunction "PB7/I2C1_SDA(5T)_93") (pintype "bidirectional"))
    )
    (net (code "75") (name "PB10") (class "Default")
      (node (ref "STM32F4") (pin "47") (pinfunction "PB10/ETH_MII_RX_ER(5T)_47") (pintype "bidirectional"))
      (node (ref "VGAHDR") (pin "1") (pinfunction "1_1") (pintype "passive"))
    )
    (net (code "76") (name "PB11") (class "Default")
      (node (ref "STM32F4") (pin "48") (pinfunction "PB11/ETH_MII_TX_EN(5T)_48") (pintype "bidirectional"))
      (node (ref "VGAHDR") (pin "2") (pinfunction "2_2") (pintype "passive"))
    )
    (net (code "77") (name "PB14") (class "Default")
      (node (ref "STM32F4") (pin "53") (pinfunction "PB14/TIM8_CH2N(5T)_53") (pintype "bidirectional"))
    )
    (net (code "78") (name "PB15") (class "Default")
      (node (ref "STM32F4") (pin "54") (pinfunction "PB15/TIM8_CH3N(5T)_54") (pintype "bidirectional"))
    )
    (net (code "79") (name "PC0") (class "Default")
      (node (ref "R17") (pin "1") (pinfunction "1_1") (pintype "passive"))
      (node (ref "STM32F4") (pin "15") (pinfunction "PC0/ADC123_IN10(5T)_15") (pintype "bidirectional"))
    )
    (net (code "80") (name "PC1") (class "Default")
      (node (ref "R16") (pin "1") (pinfunction "1_1") (pintype "passive"))
      (node (ref "STM32F4") (pin "16") (pinfunction "PC1/ETH_MDC/ADC123_IN11(5T)_16") (pintype "bidirectional"))
    )
    (net (code "81") (name "PC2") (class "Default")
      (node (ref "R19") (pin "1") (pinfunction "1_1") (pintype "passive"))
      (node (ref "STM32F4") (pin "17") (pinfunction "PC2/ETH_MII_TXD2/ADC123_IN12(5T)_17") (pintype "bidirectional"))
    )
    (net (code "82") (name "PC3") (class "Default")
      (node (ref "R18") (pin "1") (pinfunction "1_1") (pintype "passive"))
      (node (ref "STM32F4") (pin "18") (pinfunction "PC3/ETH_MII_TX_CLK/ADC123_IN13(5T)_18") (pintype "bidirectional"))
    )
    (net (code "83") (name "PC4") (class "Default")
      (node (ref "R25") (pin "1") (pinfunction "1_1") (pintype "passive"))
      (node (ref "STM32F4") (pin "33") (pinfunction "PC4/ETH_MII_RXD0/ADC12_IN14(5T)_33") (pintype "bidirectional"))
    )
    (net (code "84") (name "PC5") (class "Default")
      (node (ref "R24") (pin "1") (pinfunction "1_1") (pintype "passive"))
      (node (ref "STM32F4") (pin "34") (pinfunction "PC5/ETH_MII_RXD1/ADC12_IN15(5T)_34") (pintype "bidirectional"))
    )
    (net (code "85") (name "PC6") (class "Default")
      (node (ref "D1") (pin "A") (pinfunction "A_A") (pintype "passive"))
      (node (ref "D7") (pin "A") (pinfunction "A_A") (pintype "passive"))
      (node (ref "D9") (pin "A") (pinfunction "A_A") (pintype "passive"))
      (node (ref "STM32F4") (pin "63") (pinfunction "PC6/TIM3_CH1(5T)_63") (pintype "bidirectional"))
    )
    (net (code "86") (name "PC7") (class "Default")
      (node (ref "D10") (pin "A") (pinfunction "A_A") (pintype "passive"))
      (node (ref "D2") (pin "A") (pinfunction "A_A") (pintype "passive"))
      (node (ref "D8") (pin "A") (pinfunction "A_A") (pintype "passive"))
      (node (ref "STM32F4") (pin "64") (pinfunction "PC7/TIM8_CH2(5T)_64") (pintype "bidirectional"))
    )
    (net (code "87") (name "PC8") (class "Default")
      (node (ref "STM32F4") (pin "65") (pinfunction "PC8/TIM8_CH3(5T)_65") (pintype "bidirectional"))
    )
    (net (code "88") (name "PC9") (class "Default")
      (node (ref "STM32F4") (pin "66") (pinfunction "PC9/TIM3_CH4(5T)_66") (pintype "bidirectional"))
    )
    (net (code "89") (name "PC10") (class "Default")
      (node (ref "STM32F4") (pin "78") (pinfunction "PC10/UART4_TX(5T)_78") (pintype "bidirectional"))
    )
    (net (code "90") (name "PC11") (class "Default")
      (node (ref "STM32F4") (pin "79") (pinfunction "PC11/UART4_RX(5T)_79") (pintype "bidirectional"))
    )
    (net (code "91") (name "PC12") (class "Default")
      (node (ref "STM32F4") (pin "80") (pinfunction "PC12/UART5_TX(5T)_80") (pintype "bidirectional"))
    )
    (net (code "92") (name "PC13") (class "Default")
      (node (ref "STM32F4") (pin "7") (pinfunction "PC13(5T)_7") (pintype "bidirectional"))
    )
    (net (code "93") (name "PC14") (class "Default")
      (node (ref "STM32F4") (pin "8") (pinfunction "PC14/OSC32_IN(5T)_8") (pintype "bidirectional"))
    )
    (net (code "94") (name "PC15") (class "Default")
      (node (ref "STM32F4") (pin "9") (pinfunction "PC15/OSC32_OUT(5T)_9") (pintype "bidirectional"))
    )
    (net (code "95") (name "PH0") (class "Default")
      (node (ref "C12") (pin "1") (pinfunction "1_1") (pintype "passive"))
      (node (ref "GPUOSC") (pin "2") (pinfunction "2_2") (pintype "passive"))
      (node (ref "STM32F4") (pin "12") (pinfunction "PH0-OSC_IN(5T)_12") (pintype "bidirectional"))
    )
    (net (code "96") (name "PH1") (class "Default")
      (node (ref "C11") (pin "1") (pinfunction "1_1") (pintype "passive"))
      (node (ref "GPUOSC") (pin "1") (pinfunction "1_1") (pintype "passive"))
      (node (ref "STM32F4") (pin "13") (pinfunction "PH1-OSC_OUT(5T)_13") (pintype "bidirectional"))
    )
    (net (code "97") (name "PHI") (class "Default")
      (node (ref "EZ80F93") (pin "100") (pinfunction "PHI_100") (pintype "output"))
      (node (ref "PHI") (pin "1") (pinfunction "1_1") (pintype "passive"))
    )
    (net (code "98") (name "RTC_VDD") (class "Default")
      (node (ref "BOBMISC") (pin "6") (pinfunction "6_6") (pintype "passive"))
      (node (ref "EZ80F93") (pin "60") (pinfunction "RTC_VDD_60") (pintype "power_in"))
    )
    (net (code "99") (name "RTC_XIN") (class "Default")
      (node (ref "BOBMISC") (pin "8") (pinfunction "8_8") (pintype "passive"))
      (node (ref "EZ80F93") (pin "58") (pinfunction "RTC_XIN_58") (pintype "input"))
    )
    (net (code "100") (name "RTC_XOUT") (class "Default")
      (node (ref "BOBMISC") (pin "7") (pinfunction "7_7") (pintype "passive"))
      (node (ref "EZ80F93") (pin "59") (pinfunction "RTC_XOUT_59") (pintype "bidirectional"))
    )
    (net (code "101") (name "SCL") (class "Default")
      (node (ref "BOBI2C") (pin "1") (pinfunction "1_1") (pintype "passive"))
      (node (ref "EZ80F93") (pin "99") (pinfunction "SCL_99") (pintype "bidirectional"))
    )
    (net (code "102") (name "SDA") (class "Default")
      (node (ref "BOBI2C") (pin "2") (pinfunction "2_2") (pintype "passive"))
      (node (ref "EZ80F93") (pin "98") (pinfunction "SDA_98") (pintype "bidirectional"))
    )
    (net (code "103") (name "TCK_ZCL") (class "Default")
      (node (ref "BOBJTAG+") (pin "1") (pinfunction "1_1") (pintype "passive"))
      (node (ref "EZ80F93") (pin "63") (pinfunction "TCK/ZCL_63") (pintype "input"))
      (node (ref "ISPZDI") (pin "4") (pinfunction "4_4") (pintype "passive"))
      (node (ref "R1") (pin "2") (pinfunction "2_2") (pintype "passive"))
    )
    (net (code "104") (name "TDI_ZDA") (class "Default")
      (node (ref "BOBJTAG+") (pin "3") (pinfunction "3_3") (pintype "passive"))
      (node (ref "EZ80F93") (pin "65") (pinfunction "TDI/ZDA_65") (pintype "bidirectional"))
      (node (ref "ISPZDI") (pin "6") (pinfunction "6_6") (pintype "passive"))
      (node (ref "R6") (pin "2") (pinfunction "2_2") (pintype "passive"))
    )
    (net (code "105") (name "TDO") (class "Default")
      (node (ref "BOBJTAG+") (pin "4") (pinfunction "4_4") (pintype "passive"))
      (node (ref "EZ80F93") (pin "66") (pinfunction "TDO_66") (pintype "output"))
    )
    (net (code "106") (name "TMS") (class "Default")
      (node (ref "BOBJTAG+") (pin "2") (pinfunction "2_2") (pintype "passive"))
      (node (ref "EZ80F93") (pin "62") (pinfunction "TMS_62") (pintype "input"))
    )
    (net (code "107") (name "TRIGOUT") (class "Default")
      (node (ref "BOBJTAG+") (pin "5") (pinfunction "5_5") (pintype "passive"))
      (node (ref "EZ80F93") (pin "64") (pinfunction "TRIGOUT_64") (pintype "output"))
    )
    (net (code "108") (name "VBAT") (class "Default")
      (node (ref "STM32F4") (pin "6") (pinfunction "VBAT_6") (pintype "bidirectional"))
      (node (ref "VBATPWRJP") (pin "1") (pinfunction "1_1") (pintype "passive"))
    )
    (net (code "109") (name "VCAP_1") (class "Default")
      (node (ref "C19") (pin "1") (pinfunction "1_1") (pintype "passive"))
      (node (ref "STM32F4") (pin "49") (pinfunction "VCAP1_49") (pintype "bidirectional"))
    )
    (net (code "110") (name "VCAP_2") (class "Default")
      (node (ref "C18") (pin "1") (pinfunction "1_1") (pintype "passive"))
      (node (ref "STM32F4") (pin "73") (pinfunction "VCAP2_73") (pintype "bidirectional"))
    )
    (net (code "111") (name "VCC") (class "Default")
      (node (ref "PWRIN1") (pin "1") (pinfunction "1_1") (pintype "passive"))
      (node (ref "PWROUT1") (pin "1") (pinfunction "1_1") (pintype "passive"))
    )
    (net (code "112") (name "XIN") (class "Default")
      (node (ref "C1") (pin "1") (pinfunction "1_1") (pintype "passive"))
      (node (ref "EZ80F93") (pin "85") (pinfunction "XIN_85") (pintype "input"))
      (node (ref "R4") (pin "1") (pinfunction "1_1") (pintype "passive"))
      (node (ref "Z-OSC") (pin "1") (pinfunction "1_1") (pintype "passive"))
    )
    (net (code "113") (name "XOUT") (class "Default")
      (node (ref "EZ80F93") (pin "86") (pinfunction "XOUT_86") (pintype "output"))
      (node (ref "R2") (pin "1") (pinfunction "1_1") (pintype "passive"))
    )
    (net (code "114") (name "ZNRST") (class "Default")
      (node (ref "EZ80F93") (pin "51") (pinfunction "RESET_51") (pintype "input"))
      (node (ref "R3") (pin "1") (pinfunction "1_1") (pintype "passive"))
      (node (ref "S1") (pin "3") (pinfunction "2_3") (pintype "passive"))
    )
    (net (code "115") (name "ZPB0") (class "Default")
      (node (ref "BOBGPIOB") (pin "1") (pinfunction "1_1") (pintype "passive"))
      (node (ref "EZ80F93") (pin "88") (pinfunction "PB0/T0_IN_88") (pintype "bidirectional"))
    )
    (net (code "116") (name "ZPB1") (class "Default")
      (node (ref "BOBGPIOB") (pin "2") (pinfunction "2_2") (pintype "passive"))
      (node (ref "EZ80F93") (pin "89") (pinfunction "PB1/T1_IN_89") (pintype "bidirectional"))
    )
    (net (code "117") (name "ZPB2") (class "Default")
      (node (ref "BOBGPIOB") (pin "3") (pinfunction "3_3") (pintype "passive"))
      (node (ref "EZ80F93") (pin "90") (pinfunction "PB2/SS_90") (pintype "bidirectional"))
    )
    (net (code "118") (name "ZPB3") (class "Default")
      (node (ref "BOBGPIOB") (pin "4") (pinfunction "4_4") (pintype "passive"))
      (node (ref "EZ80F93") (pin "91") (pinfunction "PB3/SCK_91") (pintype "bidirectional"))
    )
    (net (code "119") (name "ZPB4") (class "Default")
      (node (ref "BOBGPIOB") (pin "5") (pinfunction "5_5") (pintype "passive"))
      (node (ref "EZ80F93") (pin "92") (pinfunction "PB4/T4_OUT_92") (pintype "bidirectional"))
    )
    (net (code "120") (name "ZPB5") (class "Default")
      (node (ref "BOBGPIOB") (pin "6") (pinfunction "6_6") (pintype "passive"))
      (node (ref "EZ80F93") (pin "93") (pinfunction "PB5/T5_OUT_93") (pintype "bidirectional"))
    )
    (net (code "121") (name "ZPB6") (class "Default")
      (node (ref "BOBGPIOB") (pin "7") (pinfunction "7_7") (pintype "passive"))
      (node (ref "EZ80F93") (pin "94") (pinfunction "PB6/MISO_94") (pintype "bidirectional"))
    )
    (net (code "122") (name "ZPB7") (class "Default")
      (node (ref "BOBGPIOB") (pin "8") (pinfunction "8_8") (pintype "passive"))
      (node (ref "EZ80F93") (pin "95") (pinfunction "PB7/MOSI_95") (pintype "bidirectional"))
    )
    (net (code "123") (name "ZPC0") (class "Default")
      (node (ref "EZ80F93") (pin "76") (pinfunction "PC0/TXD1_76") (pintype "bidirectional"))
      (node (ref "GPIOC-JOY0") (pin "1") (pinfunction "1_1") (pintype "passive"))
      (node (ref "R11") (pin "1") (pinfunction "1_1") (pintype "passive"))
    )
    (net (code "124") (name "ZPC1") (class "Default")
      (node (ref "EZ80F93") (pin "77") (pinfunction "PC1/RXD1_77") (pintype "bidirectional"))
      (node (ref "GPIOC-JOY0") (pin "2") (pinfunction "2_2") (pintype "passive"))
      (node (ref "R10") (pin "1") (pinfunction "1_1") (pintype "passive"))
    )
    (net (code "125") (name "ZPC2") (class "Default")
      (node (ref "EZ80F93") (pin "78") (pinfunction "PC2/RTS1_78") (pintype "bidirectional"))
      (node (ref "GPIOC-JOY0") (pin "3") (pinfunction "3_3") (pintype "passive"))
      (node (ref "R9") (pin "1") (pinfunction "1_1") (pintype "passive"))
    )
    (net (code "126") (name "ZPC3") (class "Default")
      (node (ref "EZ80F93") (pin "79") (pinfunction "PC3/CTS1_79") (pintype "bidirectional"))
      (node (ref "GPIOC-JOY0") (pin "4") (pinfunction "4_4") (pintype "passive"))
      (node (ref "R8") (pin "1") (pinfunction "1_1") (pintype "passive"))
    )
    (net (code "127") (name "ZPC4") (class "Default")
      (node (ref "EZ80F93") (pin "80") (pinfunction "PC4/DTR1_80") (pintype "bidirectional"))
      (node (ref "GPIOC-JOY0") (pin "5") (pinfunction "5_5") (pintype "passive"))
      (node (ref "R7") (pin "1") (pinfunction "1_1") (pintype "passive"))
    )
    (net (code "128") (name "ZPC5") (class "Default")
      (node (ref "EZ80F93") (pin "81") (pinfunction "PC5/DSR1_81") (pintype "bidirectional"))
      (node (ref "GPIOC-JOY0") (pin "6") (pinfunction "6_6") (pintype "passive"))
    )
    (net (code "129") (name "ZPC6") (class "Default")
      (node (ref "EZ80F93") (pin "82") (pinfunction "PC6/DCD1_82") (pintype "bidirectional"))
      (node (ref "GPIOC-JOY0") (pin "7") (pinfunction "7_7") (pintype "passive"))
      (node (ref "STM32F4") (pin "51") (pinfunction "PB12/ETH_MII_TXD0(5T)_51") (pintype "bidirectional"))
    )
    (net (code "130") (name "ZPC7") (class "Default")
      (node (ref "EZ80F93") (pin "83") (pinfunction "PC7/RI1_83") (pintype "bidirectional"))
      (node (ref "GPIOC-JOY0") (pin "8") (pinfunction "8_8") (pintype "passive"))
      (node (ref "STM32F4") (pin "52") (pinfunction "PB13/ETH_MII_TXD1(5T)_52") (pintype "bidirectional"))
    )
    (net (code "131") (name "ZPD0") (class "Default")
      (node (ref "EZ80F93") (pin "68") (pinfunction "PD0/TXD0_68") (pintype "bidirectional"))
      (node (ref "GPIOD-JOY1") (pin "1") (pinfunction "1_1") (pintype "passive"))
      (node (ref "R23") (pin "1") (pinfunction "1_1") (pintype "passive"))
    )
    (net (code "132") (name "ZPD1") (class "Default")
      (node (ref "EZ80F93") (pin "69") (pinfunction "PD1/RXD0_69") (pintype "bidirectional"))
      (node (ref "GPIOD-JOY1") (pin "2") (pinfunction "2_2") (pintype "passive"))
      (node (ref "R22") (pin "1") (pinfunction "1_1") (pintype "passive"))
    )
    (net (code "133") (name "ZPD2") (class "Default")
      (node (ref "EZ80F93") (pin "70") (pinfunction "PD2/RTS0_70") (pintype "bidirectional"))
      (node (ref "GPIOD-JOY1") (pin "3") (pinfunction "3_3") (pintype "passive"))
      (node (ref "R21") (pin "1") (pinfunction "1_1") (pintype "passive"))
    )
    (net (code "134") (name "ZPD3") (class "Default")
      (node (ref "EZ80F93") (pin "71") (pinfunction "PD3/CTS0_71") (pintype "bidirectional"))
      (node (ref "GPIOD-JOY1") (pin "4") (pinfunction "4_4") (pintype "passive"))
      (node (ref "R20") (pin "1") (pinfunction "1_1") (pintype "passive"))
    )
    (net (code "135") (name "ZPD4") (class "Default")
      (node (ref "EZ80F93") (pin "72") (pinfunction "PD4/DTR0_72") (pintype "bidirectional"))
      (node (ref "GPIOD-JOY1") (pin "5") (pinfunction "5_5") (pintype "passive"))
      (node (ref "R14") (pin "1") (pinfunction "1_1") (pintype "passive"))
    )
    (net (code "136") (name "ZPD5") (class "Default")
      (node (ref "EZ80F93") (pin "73") (pinfunction "PD5/DSR0_73") (pintype "bidirectional"))
      (node (ref "GPIOD-JOY1") (pin "6") (pinfunction "6_6") (pintype "passive"))
    )
    (net (code "137") (name "ZPD6") (class "Default")
      (node (ref "EZ80F93") (pin "74") (pinfunction "PD6/DCD0_74") (pintype "bidirectional"))
      (node (ref "GPIOD-JOY1") (pin "7") (pinfunction "7_7") (pintype "passive"))
      (node (ref "PS2KEYB") (pin "4") (pinfunction "4_4") (pintype "passive"))
      (node (ref "R33") (pin "1") (pinfunction "1_1") (pintype "passive"))
    )
    (net (code "138") (name "ZPD7") (class "Default")
      (node (ref "EZ80F93") (pin "75") (pinfunction "PD7/RI0_75") (pintype "bidirectional"))
      (node (ref "GPIOD-JOY1") (pin "8") (pinfunction "8_8") (pintype "passive"))
      (node (ref "PS2KEYB") (pin "1") (pinfunction "1_1") (pintype "passive"))
      (node (ref "R15") (pin "1") (pinfunction "1_1") (pintype "passive"))
    )
    (net (code "139") (name "unconnected-(AY-3-8913-CS2-NC-Pad16)") (class "Default")
      (node (ref "AY-3-8913-CS2") (pin "16") (pinfunction "NC_16") (pintype "no_connect"))
    )
    (net (code "140") (name "unconnected-(AY-3-8913-CS2-TEST_IN-Pad14)") (class "Default")
      (node (ref "AY-3-8913-CS2") (pin "14") (pinfunction "TEST_IN_14") (pintype "no_connect"))
    )
    (net (code "141") (name "unconnected-(AY-3-8913-CS2-TEST_OUT-Pad12)") (class "Default")
      (node (ref "AY-3-8913-CS2") (pin "12") (pinfunction "TEST_OUT_12") (pintype "no_connect"))
    )
    (net (code "142") (name "unconnected-(BOBJTAG+-Pad7)") (class "Default")
      (node (ref "BOBJTAG+") (pin "7") (pinfunction "7_7") (pintype "passive"))
    )
    (net (code "143") (name "unconnected-(BOBJTAG+-Pad8)") (class "Default")
      (node (ref "BOBJTAG+") (pin "8") (pinfunction "8_8") (pintype "passive"))
    )
    (net (code "144") (name "unconnected-(EZ80F93-INSTRD-Pad49)") (class "Default")
      (node (ref "EZ80F93") (pin "49") (pinfunction "INSTRD_49") (pintype "output"))
    )
    (net (code "145") (name "unconnected-(IC1C-O-Pad8)") (class "Default")
      (node (ref "IC1") (pin "8") (pinfunction "O_8") (pintype "output"))
    )
    (net (code "146") (name "unconnected-(IC1D-O-Pad11)") (class "Default")
      (node (ref "IC1") (pin "11") (pinfunction "O_11") (pintype "output"))
    )
    (net (code "147") (name "unconnected-(IC2C-O-Pad6)") (class "Default")
      (node (ref "IC2") (pin "6") (pinfunction "O_6") (pintype "output"))
    )
    (net (code "148") (name "unconnected-(IC2D-O-Pad8)") (class "Default")
      (node (ref "IC2") (pin "8") (pinfunction "O_8") (pintype "output"))
    )
    (net (code "149") (name "unconnected-(IC2E-O-Pad10)") (class "Default")
      (node (ref "IC2") (pin "10") (pinfunction "O_10") (pintype "output"))
    )
    (net (code "150") (name "unconnected-(IC2F-O-Pad12)") (class "Default")
      (node (ref "IC2") (pin "12") (pinfunction "O_12") (pintype "output"))
    )
    (net (code "151") (name "unconnected-(ISPJTAG-Pad4)") (class "Default")
      (node (ref "ISPJTAG") (pin "4") (pinfunction "4_4") (pintype "passive"))
    )
    (net (code "152") (name "unconnected-(ISPJTAG-Pad6)") (class "Default")
      (node (ref "ISPJTAG") (pin "6") (pinfunction "6_6") (pintype "passive"))
    )
    (net (code "153") (name "unconnected-(ISPJTAG-Pad8)") (class "Default")
      (node (ref "ISPJTAG") (pin "8") (pinfunction "8_8") (pintype "passive"))
    )
    (net (code "154") (name "unconnected-(ISPJTAG-Pad10)") (class "Default")
      (node (ref "ISPJTAG") (pin "10") (pinfunction "10_10") (pintype "passive"))
    )
    (net (code "155") (name "unconnected-(ISPJTAG-Pad11)") (class "Default")
      (node (ref "ISPJTAG") (pin "11") (pinfunction "11_11") (pintype "passive"))
    )
    (net (code "156") (name "unconnected-(ISPJTAG-Pad16)") (class "Default")
      (node (ref "ISPJTAG") (pin "16") (pinfunction "16_16") (pintype "passive"))
    )
    (net (code "157") (name "unconnected-(ISPJTAG-Pad17)") (class "Default")
      (node (ref "ISPJTAG") (pin "17") (pinfunction "17_17") (pintype "passive"))
    )
    (net (code "158") (name "unconnected-(ISPJTAG-Pad19)") (class "Default")
      (node (ref "ISPJTAG") (pin "19") (pinfunction "19_19") (pintype "passive"))
    )
    (net (code "159") (name "unconnected-(ISPZDI-Pad2)") (class "Default")
      (node (ref "ISPZDI") (pin "2") (pinfunction "2_2") (pintype "passive"))
    )
    (net (code "160") (name "unconnected-(OSCDIL14-CON-Pad1)") (class "Default")
      (node (ref "OSCDIL14") (pin "1") (pinfunction "CON_1") (pintype "input"))
    )
    (net (code "161") (name "unconnected-(RAM-CS0-NC-Pad1)") (class "Default")
      (node (ref "RAM-CS0") (pin "1") (pinfunction "NC_1") (pintype "no_connect"))
    )
    (net (code "162") (name "{slash}BUSACK") (class "Default")
      (node (ref "EZ80F93") (pin "54") (pinfunction "BUSACK_54") (pintype "output"))
      (node (ref "STM32F4") (pin "96") (pinfunction "PB9/TIM11_CH1(5T)_96") (pintype "bidirectional"))
    )
    (net (code "163") (name "{slash}BUSREQ") (class "Default")
      (node (ref "EZ80F93") (pin "53") (pinfunction "BUSREQ_53") (pintype "input"))
      (node (ref "STM32F4") (pin "95") (pinfunction "PB8/TIM10_CH1(5T)_95") (pintype "bidirectional"))
    )
    (net (code "164") (name "{slash}CS0") (class "Default")
      (node (ref "EZ80F93") (pin "29") (pinfunction "CS0_29") (pintype "output"))
      (node (ref "RAM-CS0") (pin "22") (pinfunction "CE_22") (pintype "input"))
      (node (ref "STM32F4") (pin "37") (pinfunction "PB2/BOOT1(5T)_37") (pintype "bidirectional"))
    )
    (net (code "165") (name "{slash}CS1") (class "Default")
      (node (ref "CART-CS1") (pin "PR") (pinfunction "/CE_PR") (pintype "bidirectional"))
      (node (ref "EZ80F93") (pin "30") (pinfunction "CS1_30") (pintype "output"))
      (node (ref "ISPJTAG") (pin "13") (pinfunction "13_13") (pintype "passive"))
      (node (ref "STM32F4") (pin "89") (pinfunction "PB3/JTDO(5T)_89") (pintype "bidirectional"))
    )
    (net (code "166") (name "{slash}CS2") (class "Default")
      (node (ref "AY-3-8913-CS2") (pin "24") (pinfunction "/CS_24") (pintype "input"))
      (node (ref "EZ80F93") (pin "31") (pinfunction "CS2_31") (pintype "output"))
      (node (ref "IC2") (pin "1") (pinfunction "I_1") (pintype "input"))
      (node (ref "STM32F4") (pin "90") (pinfunction "PB4/JNTRST(5T)_90") (pintype "bidirectional"))
    )
    (net (code "167") (name "{slash}CS3") (class "Default")
      (node (ref "/CS3") (pin "1") (pinfunction "1_1") (pintype "passive"))
      (node (ref "EZ80F93") (pin "32") (pinfunction "CS3_32") (pintype "output"))
      (node (ref "STM32F4") (pin "61") (pinfunction "PD14/TIM4_CH3(5T)_61") (pintype "bidirectional"))
    )
    (net (code "168") (name "{slash}IOREQ") (class "Default")
      (node (ref "BOBMISC") (pin "4") (pinfunction "4_4") (pintype "passive"))
      (node (ref "EZ80F93") (pin "45") (pinfunction "IORQ_45") (pintype "bidirectional"))
      (node (ref "R13") (pin "2") (pinfunction "2_2") (pintype "passive"))
      (node (ref "STM32F4") (pin "62") (pinfunction "PD15/TIM4_CH4(5T)_62") (pintype "bidirectional"))
    )
    (net (code "169") (name "{slash}MEMREAD") (class "Default")
      (node (ref "CART-CS1") (pin "P17") (pinfunction "/OE_P17") (pintype "bidirectional"))
      (node (ref "IC1") (pin "6") (pinfunction "O_6") (pintype "output"))
      (node (ref "RAM-CS0") (pin "24") (pinfunction "OE_24") (pintype "input"))
      (node (ref "STM32F4") (pin "35") (pinfunction "PB0/ETH_MII_RXD2/ADC12_IN8(5T)_35") (pintype "bidirectional"))
    )
    (net (code "170") (name "{slash}MEMWRITE") (class "Default")
      (node (ref "CART-CS1") (pin "PQ") (pinfunction "/WE_PQ") (pintype "bidirectional"))
      (node (ref "IC1") (pin "3") (pinfunction "O_3") (pintype "output"))
      (node (ref "IC2") (pin "3") (pinfunction "I_3") (pintype "input"))
      (node (ref "RAM-CS0") (pin "29") (pinfunction "WE_29") (pintype "input"))
      (node (ref "STM32F4") (pin "36") (pinfunction "PB1/ETH_MII_RXD3/ADC12_IN9(5T)_36") (pintype "bidirectional"))
    )
    (net (code "171") (name "{slash}MREQ") (class "Default")
      (node (ref "EZ80F93") (pin "46") (pinfunction "MREQ_46") (pintype "bidirectional"))
      (node (ref "IC1") (pin "2") (pinfunction "I1_2") (pintype "input"))
      (node (ref "IC1") (pin "4") (pinfunction "I0_4") (pintype "input"))
      (node (ref "STM32F4") (pin "91") (pinfunction "PB5/TIM3_CH2(5T)_91") (pintype "bidirectional"))
    )
    (net (code "172") (name "{slash}RD") (class "Default")
      (node (ref "BOBMISC") (pin "3") (pinfunction "3_3") (pintype "passive"))
      (node (ref "EZ80F93") (pin "47") (pinfunction "RD_47") (pintype "output"))
      (node (ref "IC1") (pin "5") (pinfunction "I1_5") (pintype "input"))
    )
    (net (code "173") (name "{slash}WR") (class "Default")
      (node (ref "BOBMISC") (pin "5") (pinfunction "5_5") (pintype "passive"))
      (node (ref "EZ80F93") (pin "48") (pinfunction "WR_48") (pintype "output"))
      (node (ref "IC1") (pin "1") (pinfunction "I0_1") (pintype "input"))
    )
  )
)
